# 15_BoardPowerSupply.net
KiCad netlist of a schematic drawn in Altium Designer
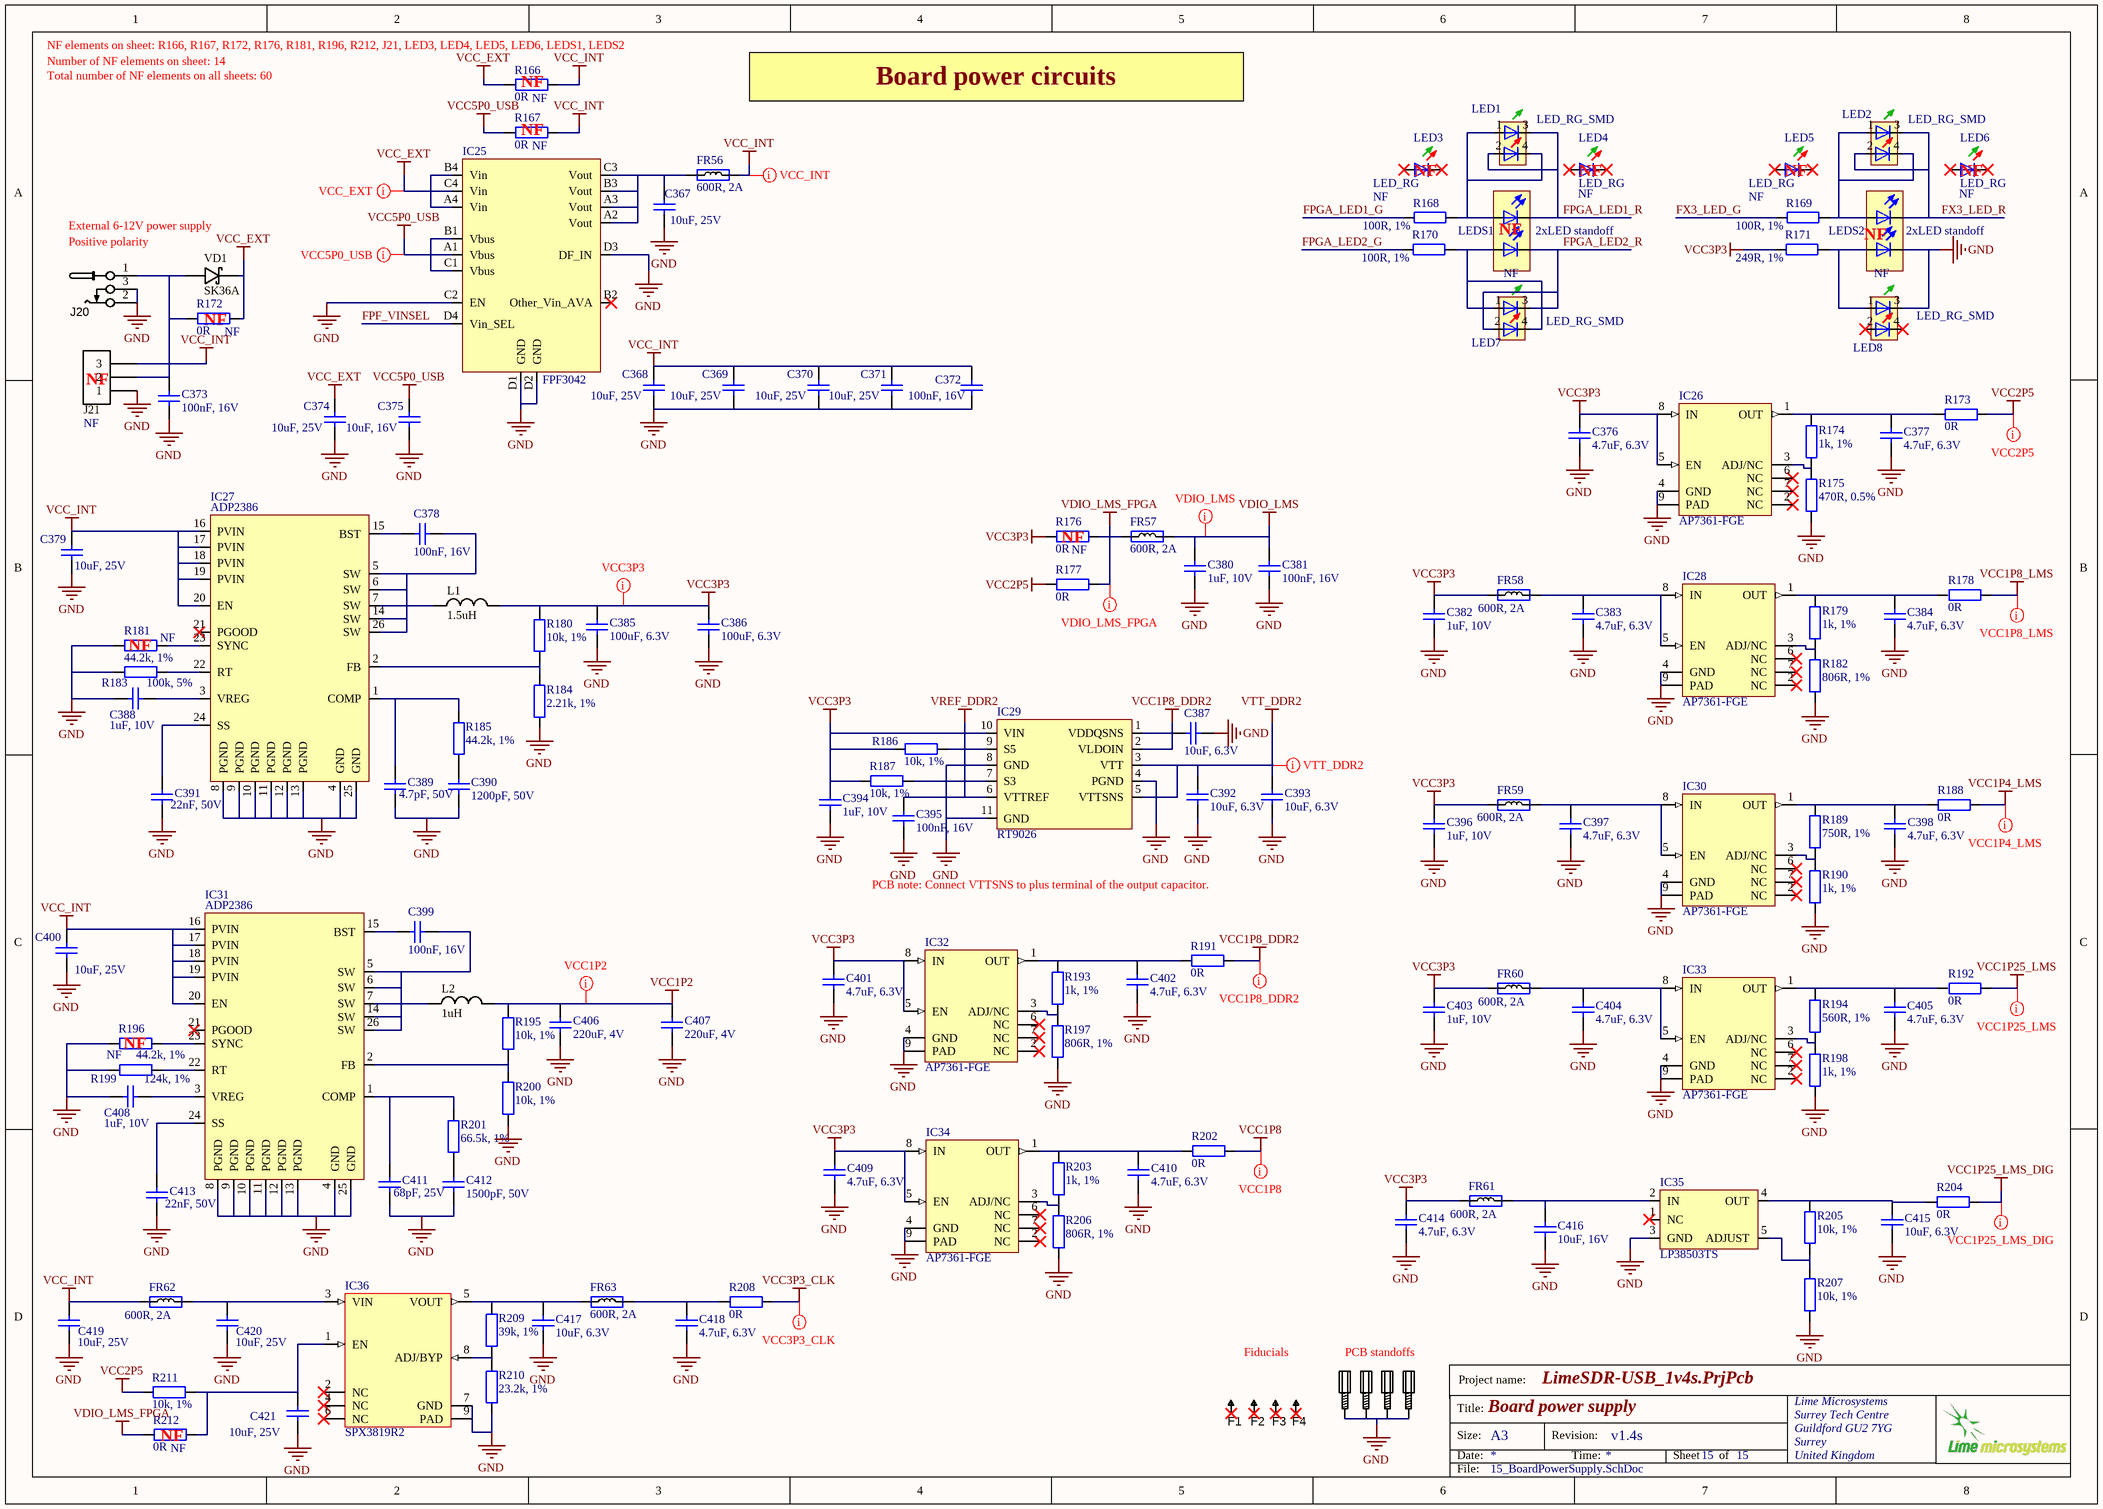
[diagram p0: 15_BoardPowerSupply.SchDoc]

(export (version "E")
  (design (tool "Eeschema 10.0.6"))
  (components
    (comp (ref "C367")
      (value "10uF, 25V")
      (footprint "CAP0603")
      (fields
        (field (name "MANUFACTURER") "Murata Electronics North America")
        (field (name "MANUFACTURER PART NUMBER") "GRM188R61E106MA73D")
        (field (name "TOLERANCE") "±20%")
      )
      (libsource (lib "LimeMicroAltiumLib_schLib") (part "Cap_0603"))
    )
    (comp (ref "C368")
      (value "10uF, 25V")
      (footprint "CAP0603")
      (fields
        (field (name "MANUFACTURER") "Murata Electronics North America")
        (field (name "MANUFACTURER PART NUMBER") "GRM188R61E106MA73D")
        (field (name "TOLERANCE") "±20%")
      )
      (libsource (lib "LimeMicroAltiumLib_schLib") (part "Cap_0603"))
    )
    (comp (ref "C369")
      (value "10uF, 25V")
      (footprint "CAP0603")
      (fields
        (field (name "MANUFACTURER") "Murata Electronics North America")
        (field (name "MANUFACTURER PART NUMBER") "GRM188R61E106MA73D")
        (field (name "TOLERANCE") "±20%")
      )
      (libsource (lib "LimeMicroAltiumLib_schLib") (part "Cap_0603"))
    )
    (comp (ref "C370")
      (value "10uF, 25V")
      (footprint "CAP0603")
      (fields
        (field (name "MANUFACTURER") "Murata Electronics North America")
        (field (name "MANUFACTURER PART NUMBER") "GRM188R61E106MA73D")
        (field (name "TOLERANCE") "±20%")
      )
      (libsource (lib "LimeMicroAltiumLib_schLib") (part "Cap_0603"))
    )
    (comp (ref "C371")
      (value "10uF, 25V")
      (footprint "CAP0603")
      (fields
        (field (name "MANUFACTURER") "Murata Electronics North America")
        (field (name "MANUFACTURER PART NUMBER") "GRM188R61E106MA73D")
        (field (name "TOLERANCE") "±20%")
      )
      (libsource (lib "LimeMicroAltiumLib_schLib") (part "Cap_0603"))
    )
    (comp (ref "C372")
      (value "100nF, 16V")
      (footprint "CAP0402")
      (fields
        (field (name "MANUFACTURER") "Murata Electronics")
        (field (name "TOLERANCE") "10 %")
        (field (name "MANUFACTURER PART NUMBER") "GRM155R71C104KA88D")
      )
      (libsource (lib "LimeMicroAltiumLib_schLib") (part "Cap_0402"))
    )
    (comp (ref "C373")
      (value "100nF, 16V")
      (footprint "CAP0402")
      (fields
        (field (name "MANUFACTURER") "Murata Electronics")
        (field (name "TOLERANCE") "10 %")
        (field (name "MANUFACTURER PART NUMBER") "GRM155R71C104KA88D")
      )
      (libsource (lib "LimeMicroAltiumLib_schLib") (part "Cap_0402"))
    )
    (comp (ref "C374")
      (value "10uF, 25V")
      (footprint "CAP0603")
      (fields
        (field (name "MANUFACTURER") "Murata Electronics North America")
        (field (name "MANUFACTURER PART NUMBER") "GRM188R61E106MA73D")
        (field (name "TOLERANCE") "±20%")
      )
      (libsource (lib "LimeMicroAltiumLib_schLib") (part "Cap_0603"))
    )
    (comp (ref "C375")
      (value "10uF, 16V")
      (footprint "CAP0603")
      (fields (field (name "MANUFACTURER") "Yageo") (field (name "TOLERANCE") "±20%"))
      (libsource (lib "LimeMicroAltiumLib_schLib") (part "Cap_0603"))
    )
    (comp (ref "C376")
      (value "4.7uF, 6.3V")
      (footprint "CAP0402")
      (fields
        (field (name "MANUFACTURER") "Murata Electronics North America")
        (field (name "TOLERANCE") "±20%")
        (field (name "MANUFACTURER PART NUMBER") "GRM155R60J475ME87D")
      )
      (libsource (lib "LimeMicroAltiumLib_schLib") (part "Cap_0402"))
    )
    (comp (ref "C377")
      (value "4.7uF, 6.3V")
      (footprint "CAP0402")
      (fields
        (field (name "MANUFACTURER") "Murata Electronics North America")
        (field (name "TOLERANCE") "±20%")
        (field (name "MANUFACTURER PART NUMBER") "GRM155R60J475ME87D")
      )
      (libsource (lib "LimeMicroAltiumLib_schLib") (part "Cap_0402"))
    )
    (comp (ref "C378")
      (value "100nF, 16V")
      (footprint "CAP0402")
      (fields
        (field (name "MANUFACTURER") "Murata Electronics")
        (field (name "TOLERANCE") "10 %")
        (field (name "MANUFACTURER PART NUMBER") "GRM155R71C104KA88D")
      )
      (libsource (lib "LimeMicroAltiumLib_schLib") (part "Cap_0402"))
    )
    (comp (ref "C379")
      (value "10uF, 25V")
      (footprint "CAP0603")
      (fields
        (field (name "MANUFACTURER") "Murata Electronics North America")
        (field (name "MANUFACTURER PART NUMBER") "GRM188R61E106MA73D")
        (field (name "TOLERANCE") "±20%")
      )
      (libsource (lib "LimeMicroAltiumLib_schLib") (part "Cap_0603"))
    )
    (comp (ref "C380")
      (value "1uF, 10V")
      (footprint "CAP0402")
      (fields (field (name "MANUFACTURER") "TDK"))
      (libsource (lib "LimeMicroAltiumLib_schLib") (part "Cap_0402"))
    )
    (comp (ref "C381")
      (value "100nF, 16V")
      (footprint "CAP0402")
      (fields
        (field (name "MANUFACTURER") "Murata Electronics")
        (field (name "TOLERANCE") "10 %")
        (field (name "MANUFACTURER PART NUMBER") "GRM155R71C104KA88D")
      )
      (libsource (lib "LimeMicroAltiumLib_schLib") (part "Cap_0402"))
    )
    (comp (ref "C382")
      (value "1uF, 10V")
      (footprint "CAP0402")
      (fields (field (name "MANUFACTURER") "TDK"))
      (libsource (lib "LimeMicroAltiumLib_schLib") (part "Cap_0402"))
    )
    (comp (ref "C383")
      (value "4.7uF, 6.3V")
      (footprint "CAP0402")
      (fields
        (field (name "MANUFACTURER") "Murata Electronics North America")
        (field (name "TOLERANCE") "±20%")
        (field (name "MANUFACTURER PART NUMBER") "GRM155R60J475ME87D")
      )
      (libsource (lib "LimeMicroAltiumLib_schLib") (part "Cap_0402"))
    )
    (comp (ref "C384")
      (value "4.7uF, 6.3V")
      (footprint "CAP0402")
      (fields
        (field (name "MANUFACTURER") "Murata Electronics North America")
        (field (name "TOLERANCE") "±20%")
        (field (name "MANUFACTURER PART NUMBER") "GRM155R60J475ME87D")
      )
      (libsource (lib "LimeMicroAltiumLib_schLib") (part "Cap_0402"))
    )
    (comp (ref "C385")
      (value "100uF, 6.3V")
      (footprint "CAP1206")
      (fields (field (name "MANUFACTURER") "Murata Electronics North America"))
      (libsource (lib "LimeFPGAboard_schLib") (part "Cap_1206"))
    )
    (comp (ref "C386")
      (value "100uF, 6.3V")
      (footprint "CAP1206")
      (fields (field (name "MANUFACTURER") "Murata Electronics North America"))
      (libsource (lib "LimeFPGAboard_schLib") (part "Cap_1206"))
    )
    (comp (ref "C387")
      (value "10uF, 6.3V")
      (footprint "CAP0603")
      (fields (field (name "TOLERANCE") "±20%") (field (name "MANUFACTURER") "Yageo"))
      (libsource (lib "LimeFPGAboard_schLib") (part "Cap_0603"))
    )
    (comp (ref "C388")
      (value "1uF, 10V")
      (footprint "CAP0402")
      (fields (field (name "MANUFACTURER") "TDK"))
      (libsource (lib "LimeMicroAltiumLib_schLib") (part "Cap_0402"))
    )
    (comp (ref "C389")
      (value "4.7pF, 50V")
      (footprint "CAP0402")
      (fields (field (name "MANUFACTURER") "Murata Electronics North America"))
      (libsource (lib "LimeMicroAltiumLib_schLib") (part "Cap_0402"))
    )
    (comp (ref "C390")
      (value "1200pF, 50V")
      (footprint "CAP0402")
      (fields (field (name "MANUFACTURER") "Kemet") (field (name "TOLERANCE") "±5%"))
      (libsource (lib "LimeMicroAltiumLib_schLib") (part "Cap_0402"))
    )
    (comp (ref "C391")
      (value "22nF, 50V")
      (footprint "CAP0402")
      (fields (field (name "TOLERANCE") "±10%") (field (name "MANUFACTURER") "Kemet"))
      (libsource (lib "LimeMicroAltiumLib_schLib") (part "Cap_0402"))
    )
    (comp (ref "C392")
      (value "10uF, 6.3V")
      (footprint "CAP0603")
      (fields (field (name "TOLERANCE") "±20%") (field (name "MANUFACTURER") "Yageo"))
      (libsource (lib "LimeFPGAboard_schLib") (part "Cap_0603"))
    )
    (comp (ref "C393")
      (value "10uF, 6.3V")
      (footprint "CAP0603")
      (fields (field (name "TOLERANCE") "±20%") (field (name "MANUFACTURER") "Yageo"))
      (libsource (lib "LimeFPGAboard_schLib") (part "Cap_0603"))
    )
    (comp (ref "C394")
      (value "1uF, 10V")
      (footprint "CAP0402")
      (fields (field (name "MANUFACTURER") "TDK"))
      (libsource (lib "LimeMicroAltiumLib_schLib") (part "Cap_0402"))
    )
    (comp (ref "C395")
      (value "100nF, 16V")
      (footprint "CAP0402")
      (fields
        (field (name "MANUFACTURER") "Murata Electronics")
        (field (name "TOLERANCE") "10 %")
        (field (name "MANUFACTURER PART NUMBER") "GRM155R71C104KA88D")
      )
      (libsource (lib "LimeMicroAltiumLib_schLib") (part "Cap_0402"))
    )
    (comp (ref "C396")
      (value "1uF, 10V")
      (footprint "CAP0402")
      (fields (field (name "MANUFACTURER") "TDK"))
      (libsource (lib "LimeMicroAltiumLib_schLib") (part "Cap_0402"))
    )
    (comp (ref "C397")
      (value "4.7uF, 6.3V")
      (footprint "CAP0402")
      (fields
        (field (name "MANUFACTURER") "Murata Electronics North America")
        (field (name "TOLERANCE") "±20%")
        (field (name "MANUFACTURER PART NUMBER") "GRM155R60J475ME87D")
      )
      (libsource (lib "LimeMicroAltiumLib_schLib") (part "Cap_0402"))
    )
    (comp (ref "C398")
      (value "4.7uF, 6.3V")
      (footprint "CAP0402")
      (fields
        (field (name "MANUFACTURER") "Murata Electronics North America")
        (field (name "TOLERANCE") "±20%")
        (field (name "MANUFACTURER PART NUMBER") "GRM155R60J475ME87D")
      )
      (libsource (lib "LimeMicroAltiumLib_schLib") (part "Cap_0402"))
    )
    (comp (ref "C399")
      (value "100nF, 16V")
      (footprint "CAP0402")
      (fields
        (field (name "MANUFACTURER") "Murata Electronics")
        (field (name "TOLERANCE") "10 %")
        (field (name "MANUFACTURER PART NUMBER") "GRM155R71C104KA88D")
      )
      (libsource (lib "LimeMicroAltiumLib_schLib") (part "Cap_0402"))
    )
    (comp (ref "C400")
      (value "10uF, 25V")
      (footprint "CAP0603")
      (fields
        (field (name "MANUFACTURER") "Murata Electronics North America")
        (field (name "MANUFACTURER PART NUMBER") "GRM188R61E106MA73D")
        (field (name "TOLERANCE") "±20%")
      )
      (libsource (lib "LimeMicroAltiumLib_schLib") (part "Cap_0603"))
    )
    (comp (ref "C401")
      (value "4.7uF, 6.3V")
      (footprint "CAP0402")
      (fields
        (field (name "MANUFACTURER") "Murata Electronics North America")
        (field (name "TOLERANCE") "±20%")
        (field (name "MANUFACTURER PART NUMBER") "GRM155R60J475ME87D")
      )
      (libsource (lib "LimeMicroAltiumLib_schLib") (part "Cap_0402"))
    )
    (comp (ref "C402")
      (value "4.7uF, 6.3V")
      (footprint "CAP0402")
      (fields
        (field (name "MANUFACTURER") "Murata Electronics North America")
        (field (name "TOLERANCE") "±20%")
        (field (name "MANUFACTURER PART NUMBER") "GRM155R60J475ME87D")
      )
      (libsource (lib "LimeMicroAltiumLib_schLib") (part "Cap_0402"))
    )
    (comp (ref "C403")
      (value "1uF, 10V")
      (footprint "CAP0402")
      (fields (field (name "MANUFACTURER") "TDK"))
      (libsource (lib "LimeMicroAltiumLib_schLib") (part "Cap_0402"))
    )
    (comp (ref "C404")
      (value "4.7uF, 6.3V")
      (footprint "CAP0402")
      (fields
        (field (name "MANUFACTURER") "Murata Electronics North America")
        (field (name "TOLERANCE") "±20%")
        (field (name "MANUFACTURER PART NUMBER") "GRM155R60J475ME87D")
      )
      (libsource (lib "LimeMicroAltiumLib_schLib") (part "Cap_0402"))
    )
    (comp (ref "C405")
      (value "4.7uF, 6.3V")
      (footprint "CAP0402")
      (fields
        (field (name "MANUFACTURER") "Murata Electronics North America")
        (field (name "TOLERANCE") "±20%")
        (field (name "MANUFACTURER PART NUMBER") "GRM155R60J475ME87D")
      )
      (libsource (lib "LimeMicroAltiumLib_schLib") (part "Cap_0402"))
    )
    (comp (ref "C406")
      (value "220uF, 4V")
      (footprint "CAP1206")
      (fields
        (field (name "MANUFACTURER") "Murata Electronics North America")
        (field (name "TOLERANCE") "±20%")
        (field (name "MANUFACTURER PART NUMBER") "GRM31CR60G227ME11L")
      )
      (libsource (lib "LimeFPGAboard_schLib") (part "Cap_1206"))
    )
    (comp (ref "C407")
      (value "220uF, 4V")
      (footprint "CAP1206")
      (fields
        (field (name "MANUFACTURER") "Murata Electronics North America")
        (field (name "TOLERANCE") "±20%")
        (field (name "MANUFACTURER PART NUMBER") "GRM31CR60G227ME11L")
      )
      (libsource (lib "LimeFPGAboard_schLib") (part "Cap_1206"))
    )
    (comp (ref "C408")
      (value "1uF, 10V")
      (footprint "CAP0402")
      (fields (field (name "MANUFACTURER") "TDK"))
      (libsource (lib "LimeMicroAltiumLib_schLib") (part "Cap_0402"))
    )
    (comp (ref "C409")
      (value "4.7uF, 6.3V")
      (footprint "CAP0402")
      (fields
        (field (name "MANUFACTURER") "Murata Electronics North America")
        (field (name "TOLERANCE") "±20%")
        (field (name "MANUFACTURER PART NUMBER") "GRM155R60J475ME87D")
      )
      (libsource (lib "LimeMicroAltiumLib_schLib") (part "Cap_0402"))
    )
    (comp (ref "C410")
      (value "4.7uF, 6.3V")
      (footprint "CAP0402")
      (fields
        (field (name "MANUFACTURER") "Murata Electronics North America")
        (field (name "TOLERANCE") "±20%")
        (field (name "MANUFACTURER PART NUMBER") "GRM155R60J475ME87D")
      )
      (libsource (lib "LimeMicroAltiumLib_schLib") (part "Cap_0402"))
    )
    (comp (ref "C411")
      (value "68pF, 25V")
      (footprint "CAP0402")
      (fields (field (name "TOLERANCE") "±1%") (field (name "MANUFACTURER") "Kemet"))
      (libsource (lib "LimeMicroAltiumLib_schLib") (part "Cap_0402"))
    )
    (comp (ref "C412")
      (value "1500pF, 50V")
      (footprint "CAP0402")
      (fields
        (field (name "MANUFACTURER") "Samsung Electro-Mechanics America, Inc.")
        (field (name "TOLERANCE") "±10%")
      )
      (libsource (lib "LimeMicroAltiumLib_schLib") (part "Cap_0402"))
    )
    (comp (ref "C413")
      (value "22nF, 50V")
      (footprint "CAP0402")
      (fields (field (name "TOLERANCE") "±10%") (field (name "MANUFACTURER") "Kemet"))
      (libsource (lib "LimeMicroAltiumLib_schLib") (part "Cap_0402"))
    )
    (comp (ref "C414")
      (value "4.7uF, 6.3V")
      (footprint "CAP0402")
      (fields
        (field (name "MANUFACTURER") "Murata Electronics North America")
        (field (name "TOLERANCE") "±20%")
        (field (name "MANUFACTURER PART NUMBER") "GRM155R60J475ME87D")
      )
      (libsource (lib "LimeMicroAltiumLib_schLib") (part "Cap_0402"))
    )
    (comp (ref "C415")
      (value "10uF, 6.3V")
      (footprint "CAP0603")
      (fields (field (name "TOLERANCE") "±20%") (field (name "MANUFACTURER") "Yageo"))
      (libsource (lib "LimeFPGAboard_schLib") (part "Cap_0603"))
    )
    (comp (ref "C416")
      (value "10uF, 16V")
      (footprint "CAP0603")
      (fields (field (name "MANUFACTURER") "Yageo") (field (name "TOLERANCE") "±20%"))
      (libsource (lib "LimeMicroAltiumLib_schLib") (part "Cap_0603"))
    )
    (comp (ref "C417")
      (value "10uF, 6.3V")
      (footprint "CAP0603")
      (fields (field (name "TOLERANCE") "±20%") (field (name "MANUFACTURER") "Yageo"))
      (libsource (lib "LimeFPGAboard_schLib") (part "Cap_0603"))
    )
    (comp (ref "C418")
      (value "4.7uF, 6.3V")
      (footprint "CAP0402")
      (fields
        (field (name "MANUFACTURER") "Murata Electronics North America")
        (field (name "TOLERANCE") "±20%")
        (field (name "MANUFACTURER PART NUMBER") "GRM155R60J475ME87D")
      )
      (libsource (lib "LimeMicroAltiumLib_schLib") (part "Cap_0402"))
    )
    (comp (ref "C419")
      (value "10uF, 25V")
      (footprint "CAP0603")
      (fields
        (field (name "MANUFACTURER") "Murata Electronics North America")
        (field (name "MANUFACTURER PART NUMBER") "GRM188R61E106MA73D")
        (field (name "TOLERANCE") "±20%")
      )
      (libsource (lib "LimeMicroAltiumLib_schLib") (part "Cap_0603"))
    )
    (comp (ref "C420")
      (value "10uF, 25V")
      (footprint "CAP0603")
      (fields
        (field (name "MANUFACTURER") "Murata Electronics North America")
        (field (name "MANUFACTURER PART NUMBER") "GRM188R61E106MA73D")
        (field (name "TOLERANCE") "±20%")
      )
      (libsource (lib "LimeMicroAltiumLib_schLib") (part "Cap_0603"))
    )
    (comp (ref "C421")
      (value "10uF, 25V")
      (footprint "CAP0603")
      (fields
        (field (name "MANUFACTURER") "Murata Electronics North America")
        (field (name "MANUFACTURER PART NUMBER") "GRM188R61E106MA73D")
        (field (name "TOLERANCE") "±20%")
      )
      (libsource (lib "LimeMicroAltiumLib_schLib") (part "Cap_0603"))
    )
    (comp (ref "F1")
      (value "Fiducial")
      (footprint "Fiducial")
      (libsource (lib "VGTU_Altium_lib") (part "Fiducial"))
    )
    (comp (ref "F2")
      (value "Fiducial")
      (footprint "Fiducial")
      (libsource (lib "VGTU_Altium_lib") (part "Fiducial"))
    )
    (comp (ref "F3")
      (value "Fiducial")
      (footprint "Fiducial")
      (libsource (lib "VGTU_Altium_lib") (part "Fiducial"))
    )
    (comp (ref "F4")
      (value "Fiducial")
      (footprint "Fiducial")
      (libsource (lib "VGTU_Altium_lib") (part "Fiducial"))
    )
    (comp (ref "FR56")
      (value "600R, 2A")
      (footprint "RES0805")
      (fields (field (name "MANUFACTURER") "TDK Corporation"))
      (libsource (lib "LimeFPGAboard_schLib") (part "Ferrite"))
    )
    (comp (ref "FR57")
      (value "600R, 2A")
      (footprint "RES0805")
      (fields (field (name "MANUFACTURER") "TDK Corporation"))
      (libsource (lib "LimeMicroAltiumLib_schLib") (part "Ferrite"))
    )
    (comp (ref "FR58")
      (value "600R, 2A")
      (footprint "RES0805")
      (fields (field (name "MANUFACTURER") "TDK Corporation"))
      (libsource (lib "LimeMicroAltiumLib_schLib") (part "Ferrite"))
    )
    (comp (ref "FR59")
      (value "600R, 2A")
      (footprint "RES0805")
      (fields (field (name "MANUFACTURER") "TDK Corporation"))
      (libsource (lib "LimeMicroAltiumLib_schLib") (part "Ferrite"))
    )
    (comp (ref "FR60")
      (value "600R, 2A")
      (footprint "RES0805")
      (fields (field (name "MANUFACTURER") "TDK Corporation"))
      (libsource (lib "LimeMicroAltiumLib_schLib") (part "Ferrite"))
    )
    (comp (ref "FR61")
      (value "600R, 2A")
      (footprint "RES0805")
      (fields (field (name "MANUFACTURER") "TDK Corporation"))
      (libsource (lib "LimeMicroAltiumLib_schLib") (part "Ferrite"))
    )
    (comp (ref "FR62")
      (value "600R, 2A")
      (footprint "RES0805")
      (fields (field (name "MANUFACTURER") "TDK Corporation"))
      (libsource (lib "LimeMicroAltiumLib_schLib") (part "Ferrite"))
    )
    (comp (ref "FR63")
      (value "600R, 2A")
      (footprint "RES0805")
      (fields (field (name "MANUFACTURER") "TDK Corporation"))
      (libsource (lib "LimeMicroAltiumLib_schLib") (part "Ferrite"))
    )
    (comp (ref "IC25")
      (value "FPF3042")
      (footprint "FPF3042")
      (fields (field (name "MANUFACTURER") "Fairchild Semiconductor"))
      (libsource (lib "LimeMicroAltiumLib_schLib") (part "FPF3042"))
    )
    (comp (ref "IC26")
      (value "AP7361-FGE")
      (footprint "AP7361")
      (fields
        (field (name "MANUFACTURER PART NUMBER") "AP7361-FGE-7")
        (field (name "MANUFACTURER") "Diodes Incorporated")
      )
      (libsource (lib "LimeMicroAltiumLib_schLib") (part "AP7361"))
    )
    (comp (ref "IC27")
      (value "ADP2386")
      (footprint "ADP2386")
      (fields
        (field (name "MANUFACTURER PART NUMBER") "ADP2386ACPZN-R7")
        (field (name "MANUFACTURER") "Analog Devices Inc.")
      )
      (libsource (lib "LimeMicroAltiumLib_schLib") (part "ADP2386"))
    )
    (comp (ref "IC28")
      (value "AP7361-FGE")
      (footprint "AP7361")
      (fields
        (field (name "MANUFACTURER PART NUMBER") "AP7361-FGE-7")
        (field (name "MANUFACTURER") "Diodes Incorporated")
      )
      (libsource (lib "LimeMicroAltiumLib_schLib") (part "AP7361"))
    )
    (comp (ref "IC29")
      (value "RT9026")
      (footprint "MSOP10")
      (fields (field (name "MANUFACTURER") "Richtek USA Inc."))
      (libsource (lib "LimeMicroAltiumLib_schLib") (part "RT9026"))
    )
    (comp (ref "IC30")
      (value "AP7361-FGE")
      (footprint "AP7361")
      (fields
        (field (name "MANUFACTURER PART NUMBER") "AP7361-FGE-7")
        (field (name "MANUFACTURER") "Diodes Incorporated")
      )
      (libsource (lib "LimeMicroAltiumLib_schLib") (part "AP7361"))
    )
    (comp (ref "IC31")
      (value "ADP2386")
      (footprint "ADP2386")
      (fields (field (name "MANUFACTURER") "Analog Devices Inc."))
      (libsource (lib "LimeMicroAltiumLib_schLib") (part "ADP2386"))
    )
    (comp (ref "IC32")
      (value "AP7361-FGE")
      (footprint "AP7361")
      (fields
        (field (name "MANUFACTURER PART NUMBER") "AP7361-FGE-7")
        (field (name "MANUFACTURER") "Diodes Incorporated")
      )
      (libsource (lib "LimeMicroAltiumLib_schLib") (part "AP7361"))
    )
    (comp (ref "IC33")
      (value "AP7361-FGE")
      (footprint "AP7361")
      (fields
        (field (name "MANUFACTURER PART NUMBER") "AP7361-FGE-7")
        (field (name "MANUFACTURER") "Diodes Incorporated")
      )
      (libsource (lib "LimeMicroAltiumLib_schLib") (part "AP7361"))
    )
    (comp (ref "IC34")
      (value "AP7361-FGE")
      (footprint "AP7361")
      (fields
        (field (name "MANUFACTURER PART NUMBER") "AP7361-FGE-7")
        (field (name "MANUFACTURER") "Diodes Incorporated")
      )
      (libsource (lib "LimeMicroAltiumLib_schLib") (part "AP7361"))
    )
    (comp (ref "IC35")
      (value "LP38503TS")
      (footprint "TO-263-5_v2")
      (fields
        (field (name "MANUFACTURER PART NUMBER") "LP38503TS-ADJ/NOPB")
        (field (name "MANUFACTURER") "Texas Instruments")
      )
      (libsource (lib "LimeMicroAltiumLib_schLib") (part "LP38503TS"))
    )
    (comp (ref "IC36")
      (value "SPX3819R2")
      (footprint "SPX3819R2-L/TR")
      (fields (field (name "MANUFACTURER") "Exar Corporation"))
      (libsource (lib "LimeMicroAltiumLib_schLib") (part "SPX3819R2-L/TR"))
    )
    (comp (ref "J20")
      (value "CONN_PWR_JACK_2.1x5.5mm")
      (footprint "CONN_PWR_JACK_v4")
      (description "Power Connector, THT, 2.1mm ID, 5.5mm OD")
      (fields (field (name "MANUFACTURER") "CUI Inc."))
      (libsource (lib "LimeFPGAboard_schLib") (part "CONN_PWR_JACK_2.1x5.5mm"))
    )
    (comp (ref "J21")
      (value "Header 3x1 pin")
      (footprint "HDR_1x3")
      (description "Header, 3-pin")
      (fields (field (name "ASSEMBLY INFO") "NF") (field (name "MANUFACTURER") "Amphenol FCI"))
      (libsource (lib "LimeMicroAltiumLib_schLib") (part "Header3P"))
    )
    (comp (ref "L1")
      (value "1.5uH")
      (footprint "FDVE1040_TOKO_INDUCTOR")
      (fields (field (name "MANUFACTURER") "Vishay Dale") (field (name "TOLERANCE") "±20%"))
      (libsource (lib "LimeMicroAltiumLib_schLib") (part "Inductor_0603"))
    )
    (comp (ref "L2")
      (value "1uH")
      (footprint "FDVE1040_TOKO_INDUCTOR")
      (fields (field (name "TOLERANCE") "±20%") (field (name "MANUFACTURER") "Vishay Dale"))
      (libsource (lib "LimeMicroAltiumLib_schLib") (part "Inductor_0603"))
    )
    (comp (ref "LED1")
      (value "LED_RG_SMD")
      (footprint "LED-2x0603")
      (fields (field (name "MANUFACTURER") "Avago Technologies US Inc."))
      (libsource (lib "LimeMicroAltiumLib_schLib") (part "LED_green_red_SMD"))
    )
    (comp (ref "LED2")
      (value "LED_RG_SMD")
      (footprint "LED-2x0603")
      (fields (field (name "MANUFACTURER") "Avago Technologies US Inc."))
      (libsource (lib "LimeMicroAltiumLib_schLib") (part "LED_green_red_SMD"))
    )
    (comp (ref "LED3")
      (value "LED_RG")
      (fields
        (field (name "MANUFACTURER") "Visual Communications Company - VCC")
        (field (name "ASSEMBLY INFO") "NF")
      )
      (libsource (lib "LimeMicroAltiumLib_schLib") (part "LED_green_red"))
    )
    (comp (ref "LED4")
      (value "LED_RG")
      (fields
        (field (name "MANUFACTURER") "Visual Communications Company - VCC")
        (field (name "ASSEMBLY INFO") "NF")
      )
      (libsource (lib "LimeMicroAltiumLib_schLib") (part "LED_green_red"))
    )
    (comp (ref "LED5")
      (value "LED_RG")
      (fields
        (field (name "MANUFACTURER") "Visual Communications Company - VCC")
        (field (name "ASSEMBLY INFO") "NF")
      )
      (libsource (lib "LimeMicroAltiumLib_schLib") (part "LED_green_red"))
    )
    (comp (ref "LED6")
      (value "LED_RG")
      (fields
        (field (name "MANUFACTURER") "Visual Communications Company - VCC")
        (field (name "ASSEMBLY INFO") "NF")
      )
      (libsource (lib "LimeMicroAltiumLib_schLib") (part "LED_green_red"))
    )
    (comp (ref "LED7")
      (value "LED_RG_SMD")
      (footprint "LED-2x0603")
      (fields (field (name "MANUFACTURER") "Avago Technologies US Inc."))
      (libsource (lib "LimeMicroAltiumLib_schLib") (part "LED_green_red_SMD"))
    )
    (comp (ref "LED8")
      (value "LED_RG_SMD")
      (footprint "LED-2x0603")
      (fields (field (name "MANUFACTURER") "Avago Technologies US Inc."))
      (libsource (lib "LimeMicroAltiumLib_schLib") (part "LED_green_red_SMD"))
    )
    (comp (ref "LEDS1")
      (value "2xLED standoff")
      (footprint "LED_STANDOFF_H-201C")
      (fields (field (name "MANUFACTURER") "Bivar Inc.") (field (name "ASSEMBLY INFO") "NF"))
      (libsource (lib "LimeMicroAltiumLib_schLib") (part "LEDx2_STANDOFF"))
    )
    (comp (ref "LEDS2")
      (value "2xLED standoff")
      (footprint "LED_STANDOFF_H-201C")
      (fields (field (name "MANUFACTURER") "Bivar Inc.") (field (name "ASSEMBLY INFO") "NF"))
      (libsource (lib "LimeMicroAltiumLib_schLib") (part "LEDx2_STANDOFF"))
    )
    (comp (ref "MECH1")
      (value "# pcs.")
      (footprint "PCB_standoff")
      (description "STANDOFF M/F MET 5MM HEX 10MM L")
      (fields (field (name "MANUFACTURER") "FIX&FASTEN"))
      (libsource (lib "LimeMicroAltiumLib_schLib") (part "STANDOFF_M-F_THREADED_M3x8x10mm_HEX_5mm dia"))
    )
    (comp (ref "MECH2")
      (value "# pcs.")
      (footprint "PCB_standoff")
      (description "STANDOFF M/F MET 5MM HEX 10MM L")
      (fields (field (name "MANUFACTURER") "FIX&FASTEN"))
      (libsource (lib "LimeMicroAltiumLib_schLib") (part "STANDOFF_M-F_THREADED_M3x8x10mm_HEX_5mm dia"))
    )
    (comp (ref "MECH3")
      (value "# pcs.")
      (footprint "PCB_standoff")
      (description "STANDOFF M/F MET 5MM HEX 10MM L")
      (fields (field (name "MANUFACTURER") "FIX&FASTEN"))
      (libsource (lib "LimeMicroAltiumLib_schLib") (part "STANDOFF_M-F_THREADED_M3x8x10mm_HEX_5mm dia"))
    )
    (comp (ref "MECH4")
      (value "# pcs.")
      (footprint "PCB_standoff")
      (description "STANDOFF M/F MET 5MM HEX 10MM L")
      (fields (field (name "MANUFACTURER") "FIX&FASTEN"))
      (libsource (lib "LimeMicroAltiumLib_schLib") (part "STANDOFF_M-F_THREADED_M3x8x10mm_HEX_5mm dia"))
    )
    (comp (ref "R166")
      (value "0R")
      (footprint "RES0402")
      (fields
        (field (name "ASSEMBLY INFO") "NF")
        (field (name "MANUFACTURER") "Yageo")
        (field (name "TOLERANCE") "Jumper")
      )
      (libsource (lib "LimeMicroAltiumLib_schLib") (part "Res_0402"))
    )
    (comp (ref "R167")
      (value "0R")
      (footprint "RES0402")
      (fields
        (field (name "ASSEMBLY INFO") "NF")
        (field (name "MANUFACTURER") "Yageo")
        (field (name "TOLERANCE") "Jumper")
      )
      (libsource (lib "LimeMicroAltiumLib_schLib") (part "Res_0402"))
    )
    (comp (ref "R168")
      (value "100R, 1%")
      (footprint "RES0402")
      (fields (field (name "TOLERANCE") "±1%") (field (name "MANUFACTURER") "Stackpole Electronics Inc."))
      (libsource (lib "LimeMicroAltiumLib_schLib") (part "Res_0402"))
    )
    (comp (ref "R169")
      (value "100R, 1%")
      (footprint "RES0402")
      (fields (field (name "TOLERANCE") "±1%") (field (name "MANUFACTURER") "Stackpole Electronics Inc."))
      (libsource (lib "LimeMicroAltiumLib_schLib") (part "Res_0402"))
    )
    (comp (ref "R170")
      (value "100R, 1%")
      (footprint "RES0402")
      (fields (field (name "TOLERANCE") "±1%") (field (name "MANUFACTURER") "Stackpole Electronics Inc."))
      (libsource (lib "LimeMicroAltiumLib_schLib") (part "Res_0402"))
    )
    (comp (ref "R171")
      (value "249R, 1%")
      (footprint "RES0402")
      (fields (field (name "MANUFACTURER") "Stackpole Electronics Inc") (field (name "TOLERANCE") "±1%"))
      (libsource (lib "LimeMicroAltiumLib_schLib") (part "Res_0402"))
    )
    (comp (ref "R172")
      (value "0R")
      (footprint "RES0805")
      (fields
        (field (name "ASSEMBLY INFO") "NF")
        (field (name "MANUFACTURER") "Vishay Dale")
        (field (name "TOLERANCE") "Jumper")
      )
      (libsource (lib "LimeMicroAltiumLib_schLib") (part "Res_0402"))
    )
    (comp (ref "R173")
      (value "0R")
      (footprint "RES0402")
      (fields (field (name "MANUFACTURER") "Yageo") (field (name "TOLERANCE") "Jumper"))
      (libsource (lib "LimeMicroAltiumLib_schLib") (part "Res_0402"))
    )
    (comp (ref "R174")
      (value "1k, 1%")
      (footprint "RES0402")
      (fields (field (name "MANUFACTURER") "Stackpole Electronics Inc") (field (name "TOLERANCE") "±1%"))
      (libsource (lib "LimeMicroAltiumLib_schLib") (part "Res_0402"))
    )
    (comp (ref "R175")
      (value "470R, 0.5%")
      (footprint "RES0402")
      (fields
        (field (name "TOLERANCE") "±0.5%")
        (field (name "MANUFACTURER") "Panasonic Electronic Components")
      )
      (libsource (lib "LimeMicroAltiumLib_schLib") (part "Res_0402"))
    )
    (comp (ref "R176")
      (value "0R")
      (footprint "RES0402")
      (fields
        (field (name "ASSEMBLY INFO") "NF")
        (field (name "MANUFACTURER") "Yageo")
        (field (name "TOLERANCE") "Jumper")
      )
      (libsource (lib "LimeMicroAltiumLib_schLib") (part "Res_0402"))
    )
    (comp (ref "R177")
      (value "0R")
      (footprint "RES0402")
      (fields (field (name "MANUFACTURER") "Yageo") (field (name "TOLERANCE") "Jumper"))
      (libsource (lib "LimeMicroAltiumLib_schLib") (part "Res_0402"))
    )
    (comp (ref "R178")
      (value "0R")
      (footprint "RES0402")
      (fields (field (name "MANUFACTURER") "Yageo") (field (name "TOLERANCE") "Jumper"))
      (libsource (lib "LimeMicroAltiumLib_schLib") (part "Res_0402"))
    )
    (comp (ref "R179")
      (value "1k, 1%")
      (footprint "RES0402")
      (fields (field (name "MANUFACTURER") "Stackpole Electronics Inc") (field (name "TOLERANCE") "±1%"))
      (libsource (lib "LimeMicroAltiumLib_schLib") (part "Res_0402"))
    )
    (comp (ref "R180")
      (value "10k, 1%")
      (footprint "RES0402")
      (fields (field (name "MANUFACTURER") "Yageo") (field (name "TOLERANCE") "±1%"))
      (libsource (lib "LimeMicroAltiumLib_schLib") (part "Res_0402"))
    )
    (comp (ref "R181")
      (value "44.2k, 1%")
      (footprint "RES0402")
      (fields
        (field (name "ASSEMBLY INFO") "NF")
        (field (name "TOLERANCE") "±1%")
        (field (name "MANUFACTURER") "Panasonic Electronic Components")
      )
      (libsource (lib "LimeMicroAltiumLib_schLib") (part "Res_0402"))
    )
    (comp (ref "R182")
      (value "806R, 1%")
      (footprint "RES0402")
      (fields (field (name "TOLERANCE") "±1%") (field (name "MANUFACTURER") "Stackpole Electronics Inc"))
      (libsource (lib "LimeMicroAltiumLib_schLib") (part "Res_0402"))
    )
    (comp (ref "R183")
      (value "100k, 5%")
      (footprint "RES0402")
      (fields
        (field (name "MANUFACTURER") "Panasonic Electronic Components")
        (field (name "MANUFACTURER PART NUMBER") "ERJ-2GEJ104X")
        (field (name "TOLERANCE") "±5%")
      )
      (libsource (lib "LimeMicroAltiumLib_schLib") (part "Res_0402"))
    )
    (comp (ref "R184")
      (value "2.21k, 1%")
      (footprint "RES0402")
      (fields (field (name "MANUFACTURER") "Stackpole Electronics Inc.") (field (name "TOLERANCE") "±1%"))
      (libsource (lib "LimeMicroAltiumLib_schLib") (part "Res_0402"))
    )
    (comp (ref "R185")
      (value "44.2k, 1%")
      (footprint "RES0402")
      (fields
        (field (name "TOLERANCE") "±1%")
        (field (name "MANUFACTURER") "Panasonic Electronic Components")
      )
      (libsource (lib "LimeMicroAltiumLib_schLib") (part "Res_0402"))
    )
    (comp (ref "R186")
      (value "10k, 1%")
      (footprint "RES0402")
      (fields (field (name "MANUFACTURER") "Yageo") (field (name "TOLERANCE") "±1%"))
      (libsource (lib "LimeMicroAltiumLib_schLib") (part "Res_0402"))
    )
    (comp (ref "R187")
      (value "10k, 1%")
      (footprint "RES0402")
      (fields (field (name "MANUFACTURER") "Yageo") (field (name "TOLERANCE") "±1%"))
      (libsource (lib "LimeMicroAltiumLib_schLib") (part "Res_0402"))
    )
    (comp (ref "R188")
      (value "0R")
      (footprint "RES0402")
      (fields (field (name "MANUFACTURER") "Yageo") (field (name "TOLERANCE") "Jumper"))
      (libsource (lib "LimeMicroAltiumLib_schLib") (part "Res_0402"))
    )
    (comp (ref "R189")
      (value "750R, 1%")
      (footprint "RES0402")
      (fields
        (field (name "TOLERANCE") "±1%")
        (field (name "MANUFACTURER PART NUMBER") "RC0402FR-07750RL")
        (field (name "MANUFACTURER") "Yageo")
      )
      (libsource (lib "LimeMicroAltiumLib_schLib") (part "Res_0402"))
    )
    (comp (ref "R190")
      (value "1k, 1%")
      (footprint "RES0402")
      (fields (field (name "MANUFACTURER") "Stackpole Electronics Inc") (field (name "TOLERANCE") "±1%"))
      (libsource (lib "LimeMicroAltiumLib_schLib") (part "Res_0402"))
    )
    (comp (ref "R191")
      (value "0R")
      (footprint "RES0402")
      (fields (field (name "MANUFACTURER") "Yageo") (field (name "TOLERANCE") "Jumper"))
      (libsource (lib "LimeMicroAltiumLib_schLib") (part "Res_0402"))
    )
    (comp (ref "R192")
      (value "0R")
      (footprint "RES0402")
      (fields (field (name "MANUFACTURER") "Yageo") (field (name "TOLERANCE") "Jumper"))
      (libsource (lib "LimeMicroAltiumLib_schLib") (part "Res_0402"))
    )
    (comp (ref "R193")
      (value "1k, 1%")
      (footprint "RES0402")
      (fields (field (name "MANUFACTURER") "Stackpole Electronics Inc") (field (name "TOLERANCE") "±1%"))
      (libsource (lib "LimeMicroAltiumLib_schLib") (part "Res_0402"))
    )
    (comp (ref "R194")
      (value "560R, 1%")
      (footprint "RES0402")
      (fields
        (field (name "MANUFACTURER PART NUMBER") "CRCW0402560RFKED")
        (field (name "TOLERANCE") "±1%")
        (field (name "MANUFACTURER") "Vishay Dale")
      )
      (libsource (lib "LimeMicroAltiumLib_schLib") (part "Res_0402"))
    )
    (comp (ref "R195")
      (value "10k, 1%")
      (footprint "RES0402")
      (fields (field (name "MANUFACTURER") "Yageo") (field (name "TOLERANCE") "±1%"))
      (libsource (lib "LimeMicroAltiumLib_schLib") (part "Res_0402"))
    )
    (comp (ref "R196")
      (value "44.2k, 1%")
      (footprint "RES0402")
      (fields
        (field (name "ASSEMBLY INFO") "NF")
        (field (name "TOLERANCE") "±1%")
        (field (name "MANUFACTURER") "Panasonic Electronic Components")
      )
      (libsource (lib "LimeMicroAltiumLib_schLib") (part "Res_0402"))
    )
    (comp (ref "R197")
      (value "806R, 1%")
      (footprint "RES0402")
      (fields (field (name "TOLERANCE") "±1%") (field (name "MANUFACTURER") "Stackpole Electronics Inc"))
      (libsource (lib "LimeMicroAltiumLib_schLib") (part "Res_0402"))
    )
    (comp (ref "R198")
      (value "1k, 1%")
      (footprint "RES0402")
      (fields (field (name "MANUFACTURER") "Stackpole Electronics Inc") (field (name "TOLERANCE") "±1%"))
      (libsource (lib "LimeMicroAltiumLib_schLib") (part "Res_0402"))
    )
    (comp (ref "R199")
      (value "124k, 1%")
      (footprint "RES0402")
      (fields
        (field (name "MANUFACTURER") "Panasonic Electronic Components")
        (field (name "TOLERANCE") "±1%")
      )
      (libsource (lib "LimeMicroAltiumLib_schLib") (part "Res_0402"))
    )
    (comp (ref "R200")
      (value "10k, 1%")
      (footprint "RES0402")
      (fields (field (name "MANUFACTURER") "Yageo") (field (name "TOLERANCE") "±1%"))
      (libsource (lib "LimeMicroAltiumLib_schLib") (part "Res_0402"))
    )
    (comp (ref "R201")
      (value "66.5k, 1%")
      (footprint "RES0402")
      (fields
        (field (name "MANUFACTURER") "Panasonic Electronic Components")
        (field (name "TOLERANCE") "±1%")
      )
      (libsource (lib "LimeMicroAltiumLib_schLib") (part "Res_0402"))
    )
    (comp (ref "R202")
      (value "0R")
      (footprint "RES0402")
      (fields (field (name "MANUFACTURER") "Yageo") (field (name "TOLERANCE") "Jumper"))
      (libsource (lib "LimeMicroAltiumLib_schLib") (part "Res_0402"))
    )
    (comp (ref "R203")
      (value "1k, 1%")
      (footprint "RES0402")
      (fields (field (name "MANUFACTURER") "Stackpole Electronics Inc") (field (name "TOLERANCE") "±1%"))
      (libsource (lib "LimeMicroAltiumLib_schLib") (part "Res_0402"))
    )
    (comp (ref "R204")
      (value "0R")
      (footprint "RES0402")
      (fields (field (name "MANUFACTURER") "Yageo") (field (name "TOLERANCE") "Jumper"))
      (libsource (lib "LimeMicroAltiumLib_schLib") (part "Res_0402"))
    )
    (comp (ref "R205")
      (value "10k, 1%")
      (footprint "RES0402")
      (fields (field (name "MANUFACTURER") "Yageo") (field (name "TOLERANCE") "±1%"))
      (libsource (lib "LimeMicroAltiumLib_schLib") (part "Res_0402"))
    )
    (comp (ref "R206")
      (value "806R, 1%")
      (footprint "RES0402")
      (fields (field (name "TOLERANCE") "±1%") (field (name "MANUFACTURER") "Stackpole Electronics Inc"))
      (libsource (lib "LimeMicroAltiumLib_schLib") (part "Res_0402"))
    )
    (comp (ref "R207")
      (value "10k, 1%")
      (footprint "RES0402")
      (fields (field (name "MANUFACTURER") "Yageo") (field (name "TOLERANCE") "±1%"))
      (libsource (lib "LimeMicroAltiumLib_schLib") (part "Res_0402"))
    )
    (comp (ref "R208")
      (value "0R")
      (footprint "RES0402")
      (fields (field (name "MANUFACTURER") "Yageo") (field (name "TOLERANCE") "Jumper"))
      (libsource (lib "LimeMicroAltiumLib_schLib") (part "Res_0402"))
    )
    (comp (ref "R209")
      (value "39k, 1%")
      (footprint "RES0402")
      (fields (field (name "MANUFACTURER") "Yageo") (field (name "TOLERANCE") "±1%"))
      (libsource (lib "LimeMicroAltiumLib_schLib") (part "Res_0402"))
    )
    (comp (ref "R210")
      (value "23.2k, 1%")
      (footprint "RES0402")
      (fields (field (name "TOLERANCE") "±1%") (field (name "MANUFACTURER") "Yageo"))
      (libsource (lib "LimeMicroAltiumLib_schLib") (part "Res_0402"))
    )
    (comp (ref "R211")
      (value "10k, 1%")
      (footprint "RES0402")
      (fields (field (name "MANUFACTURER") "Yageo") (field (name "TOLERANCE") "±1%"))
      (libsource (lib "LimeMicroAltiumLib_schLib") (part "Res_0402"))
    )
    (comp (ref "R212")
      (value "0R")
      (footprint "RES0402")
      (fields
        (field (name "ASSEMBLY INFO") "NF")
        (field (name "MANUFACTURER") "Yageo")
        (field (name "TOLERANCE") "Jumper")
      )
      (libsource (lib "LimeMicroAltiumLib_schLib") (part "Res_0402"))
    )
    (comp (ref "VD1")
      (value "SK36A")
      (footprint "DIODE_SMB")
      (description "Diode Schottky SMD SOD-523F")
      (fields (field (name "MANUFACTURER") "Micro Commercial Co"))
      (libsource (lib "LimeMicroAltiumLib_schLib") (part "DIODE_SCHOTTKY_SOD-523F"))
    )
  )
  (nets
    (net (code "1") (name "/FPF_VINSEL") (class "Default")
      (node (ref "IC25") (pin "D4") (pinfunction "Vin_SEL_D4") (pintype "passive"))
    )
    (net (code "2") (name "/FPGA_LED1_G") (class "Default")
      (node (ref "R168") (pin "1") (pinfunction "1_1") (pintype "passive"))
    )
    (net (code "3") (name "/FPGA_LED1_R") (class "Default")
      (node (ref "LED1") (pin "2") (pinfunction "2_2") (pintype "power_in"))
      (node (ref "LED1") (pin "3") (pinfunction "3_3") (pintype "power_in"))
      (node (ref "LEDS1") (pin "K1") (pinfunction "C_K1") (pintype "power_in"))
    )
    (net (code "4") (name "/FPGA_LED2_G") (class "Default")
      (node (ref "R170") (pin "1") (pinfunction "1_1") (pintype "passive"))
    )
    (net (code "5") (name "/FPGA_LED2_R") (class "Default")
      (node (ref "LED7") (pin "2") (pinfunction "2_2") (pintype "power_in"))
      (node (ref "LED7") (pin "3") (pinfunction "3_3") (pintype "power_in"))
      (node (ref "LEDS1") (pin "K2") (pinfunction "C_K2") (pintype "power_in"))
    )
    (net (code "6") (name "/FX3_LED_G") (class "Default")
      (node (ref "R169") (pin "1") (pinfunction "1_1") (pintype "passive"))
    )
    (net (code "7") (name "/FX3_LED_R") (class "Default")
      (node (ref "LED2") (pin "2") (pinfunction "2_2") (pintype "power_in"))
      (node (ref "LED2") (pin "3") (pinfunction "3_3") (pintype "power_in"))
      (node (ref "LEDS2") (pin "K1") (pinfunction "C_K1") (pintype "power_in"))
    )
    (net (code "8") (name "GND") (class "Default")
      (node (ref "C367") (pin "1") (pinfunction "1_1") (pintype "passive"))
      (node (ref "C368") (pin "1") (pinfunction "1_1") (pintype "passive"))
      (node (ref "C369") (pin "1") (pinfunction "1_1") (pintype "passive"))
      (node (ref "C370") (pin "1") (pinfunction "1_1") (pintype "passive"))
      (node (ref "C371") (pin "1") (pinfunction "1_1") (pintype "passive"))
      (node (ref "C372") (pin "2") (pinfunction "2_2") (pintype "passive"))
      (node (ref "C373") (pin "2") (pinfunction "2_2") (pintype "passive"))
      (node (ref "C374") (pin "1") (pinfunction "1_1") (pintype "passive"))
      (node (ref "C375") (pin "1") (pinfunction "1_1") (pintype "passive"))
      (node (ref "C376") (pin "1") (pinfunction "1_1") (pintype "passive"))
      (node (ref "C377") (pin "1") (pinfunction "1_1") (pintype "passive"))
      (node (ref "C379") (pin "1") (pinfunction "1_1") (pintype "passive"))
      (node (ref "C380") (pin "1") (pinfunction "1_1") (pintype "passive"))
      (node (ref "C381") (pin "2") (pinfunction "2_2") (pintype "passive"))
      (node (ref "C382") (pin "1") (pinfunction "1_1") (pintype "passive"))
      (node (ref "C383") (pin "1") (pinfunction "1_1") (pintype "passive"))
      (node (ref "C384") (pin "1") (pinfunction "1_1") (pintype "passive"))
      (node (ref "C385") (pin "1") (pinfunction "1_1") (pintype "passive"))
      (node (ref "C386") (pin "1") (pinfunction "1_1") (pintype "passive"))
      (node (ref "C387") (pin "1") (pinfunction "1_1") (pintype "passive"))
      (node (ref "C388") (pin "2") (pinfunction "2_2") (pintype "passive"))
      (node (ref "C389") (pin "2") (pinfunction "2_2") (pintype "passive"))
      (node (ref "C390") (pin "2") (pinfunction "2_2") (pintype "passive"))
      (node (ref "C391") (pin "2") (pinfunction "2_2") (pintype "passive"))
      (node (ref "C392") (pin "1") (pinfunction "1_1") (pintype "passive"))
      (node (ref "C393") (pin "1") (pinfunction "1_1") (pintype "passive"))
      (node (ref "C394") (pin "1") (pinfunction "1_1") (pintype "passive"))
      (node (ref "C395") (pin "2") (pinfunction "2_2") (pintype "passive"))
      (node (ref "C396") (pin "1") (pinfunction "1_1") (pintype "passive"))
      (node (ref "C397") (pin "1") (pinfunction "1_1") (pintype "passive"))
      (node (ref "C398") (pin "1") (pinfunction "1_1") (pintype "passive"))
      (node (ref "C400") (pin "1") (pinfunction "1_1") (pintype "passive"))
      (node (ref "C401") (pin "1") (pinfunction "1_1") (pintype "passive"))
      (node (ref "C402") (pin "1") (pinfunction "1_1") (pintype "passive"))
      (node (ref "C403") (pin "1") (pinfunction "1_1") (pintype "passive"))
      (node (ref "C404") (pin "1") (pinfunction "1_1") (pintype "passive"))
      (node (ref "C405") (pin "1") (pinfunction "1_1") (pintype "passive"))
      (node (ref "C406") (pin "1") (pinfunction "1_1") (pintype "passive"))
      (node (ref "C407") (pin "1") (pinfunction "1_1") (pintype "passive"))
      (node (ref "C408") (pin "2") (pinfunction "2_2") (pintype "passive"))
      (node (ref "C409") (pin "1") (pinfunction "1_1") (pintype "passive"))
      (node (ref "C410") (pin "1") (pinfunction "1_1") (pintype "passive"))
      (node (ref "C411") (pin "2") (pinfunction "2_2") (pintype "passive"))
      (node (ref "C412") (pin "2") (pinfunction "2_2") (pintype "passive"))
      (node (ref "C413") (pin "2") (pinfunction "2_2") (pintype "passive"))
      (node (ref "C414") (pin "1") (pinfunction "1_1") (pintype "passive"))
      (node (ref "C415") (pin "1") (pinfunction "1_1") (pintype "passive"))
      (node (ref "C416") (pin "1") (pinfunction "1_1") (pintype "passive"))
      (node (ref "C417") (pin "1") (pinfunction "1_1") (pintype "passive"))
      (node (ref "C418") (pin "1") (pinfunction "1_1") (pintype "passive"))
      (node (ref "C419") (pin "1") (pinfunction "1_1") (pintype "passive"))
      (node (ref "C420") (pin "1") (pinfunction "1_1") (pintype "passive"))
      (node (ref "C421") (pin "1") (pinfunction "1_1") (pintype "passive"))
      (node (ref "IC25") (pin "C2") (pinfunction "EN_C2") (pintype "passive"))
      (node (ref "IC25") (pin "D1") (pinfunction "GND_D1") (pintype "passive"))
      (node (ref "IC25") (pin "D2") (pinfunction "GND_D2") (pintype "passive"))
      (node (ref "IC25") (pin "D3") (pinfunction "DF_IN_D3") (pintype "passive"))
      (node (ref "IC26") (pin "4") (pinfunction "GND_4") (pintype "passive"))
      (node (ref "IC26") (pin "9") (pinfunction "PAD_9") (pintype "passive"))
      (node (ref "IC27") (pin "10") (pinfunction "PGND_10") (pintype "passive"))
      (node (ref "IC27") (pin "11") (pinfunction "PGND_11") (pintype "passive"))
      (node (ref "IC27") (pin "12") (pinfunction "PGND_12") (pintype "passive"))
      (node (ref "IC27") (pin "13") (pinfunction "PGND_13") (pintype "passive"))
      (node (ref "IC27") (pin "25") (pinfunction "GND_25") (pintype "passive"))
      (node (ref "IC27") (pin "4") (pinfunction "GND_4") (pintype "passive"))
      (node (ref "IC27") (pin "8") (pinfunction "PGND_8") (pintype "passive"))
      (node (ref "IC27") (pin "9") (pinfunction "PGND_9") (pintype "passive"))
      (node (ref "IC28") (pin "4") (pinfunction "GND_4") (pintype "passive"))
      (node (ref "IC28") (pin "9") (pinfunction "PAD_9") (pintype "passive"))
      (node (ref "IC29") (pin "11") (pinfunction "GND_11") (pintype "passive"))
      (node (ref "IC29") (pin "4") (pinfunction "PGND_4") (pintype "passive"))
      (node (ref "IC29") (pin "8") (pinfunction "GND_8") (pintype "passive"))
      (node (ref "IC30") (pin "4") (pinfunction "GND_4") (pintype "passive"))
      (node (ref "IC30") (pin "9") (pinfunction "PAD_9") (pintype "passive"))
      (node (ref "IC31") (pin "10") (pinfunction "PGND_10") (pintype "passive"))
      (node (ref "IC31") (pin "11") (pinfunction "PGND_11") (pintype "passive"))
      (node (ref "IC31") (pin "12") (pinfunction "PGND_12") (pintype "passive"))
      (node (ref "IC31") (pin "13") (pinfunction "PGND_13") (pintype "passive"))
      (node (ref "IC31") (pin "25") (pinfunction "GND_25") (pintype "passive"))
      (node (ref "IC31") (pin "4") (pinfunction "GND_4") (pintype "passive"))
      (node (ref "IC31") (pin "8") (pinfunction "PGND_8") (pintype "passive"))
      (node (ref "IC31") (pin "9") (pinfunction "PGND_9") (pintype "passive"))
      (node (ref "IC32") (pin "4") (pinfunction "GND_4") (pintype "passive"))
      (node (ref "IC32") (pin "9") (pinfunction "PAD_9") (pintype "passive"))
      (node (ref "IC33") (pin "4") (pinfunction "GND_4") (pintype "passive"))
      (node (ref "IC33") (pin "9") (pinfunction "PAD_9") (pintype "passive"))
      (node (ref "IC34") (pin "4") (pinfunction "GND_4") (pintype "passive"))
      (node (ref "IC34") (pin "9") (pinfunction "PAD_9") (pintype "passive"))
      (node (ref "IC35") (pin "3") (pinfunction "GND_3") (pintype "passive"))
      (node (ref "IC36") (pin "7") (pinfunction "GND_7") (pintype "passive"))
      (node (ref "IC36") (pin "9") (pinfunction "PAD_9") (pintype "passive"))
      (node (ref "J20") (pin "2") (pinfunction "2_2") (pintype "passive"))
      (node (ref "J20") (pin "3") (pinfunction "3_3") (pintype "passive"))
      (node (ref "J21") (pin "1") (pinfunction "1_1") (pintype "passive"))
      (node (ref "LED8") (pin "3") (pinfunction "3_3") (pintype "power_in"))
      (node (ref "LEDS2") (pin "K2") (pinfunction "C_K2") (pintype "power_in"))
      (node (ref "MECH1") (pin "MH1") (pinfunction "MH1_MH1") (pintype "passive"))
      (node (ref "MECH2") (pin "MH1") (pinfunction "MH1_MH1") (pintype "passive"))
      (node (ref "MECH3") (pin "MH1") (pinfunction "MH1_MH1") (pintype "passive"))
      (node (ref "MECH4") (pin "MH1") (pinfunction "MH1_MH1") (pintype "passive"))
      (node (ref "R175") (pin "2") (pinfunction "2_2") (pintype "passive"))
      (node (ref "R181") (pin "2") (pinfunction "2_2") (pintype "passive"))
      (node (ref "R182") (pin "2") (pinfunction "2_2") (pintype "passive"))
      (node (ref "R183") (pin "2") (pinfunction "2_2") (pintype "passive"))
      (node (ref "R184") (pin "1") (pinfunction "1_1") (pintype "passive"))
      (node (ref "R190") (pin "1") (pinfunction "1_1") (pintype "passive"))
      (node (ref "R196") (pin "2") (pinfunction "2_2") (pintype "passive"))
      (node (ref "R197") (pin "2") (pinfunction "2_2") (pintype "passive"))
      (node (ref "R198") (pin "1") (pinfunction "1_1") (pintype "passive"))
      (node (ref "R199") (pin "2") (pinfunction "2_2") (pintype "passive"))
      (node (ref "R200") (pin "2") (pinfunction "2_2") (pintype "passive"))
      (node (ref "R206") (pin "2") (pinfunction "2_2") (pintype "passive"))
      (node (ref "R207") (pin "2") (pinfunction "2_2") (pintype "passive"))
      (node (ref "R210") (pin "1") (pinfunction "1_1") (pintype "passive"))
    )
    (net (code "9") (name "Net-(C367-Pad2)") (class "Default")
      (node (ref "C367") (pin "2") (pinfunction "2_2") (pintype "passive"))
      (node (ref "FR56") (pin "2") (pinfunction "2_2") (pintype "passive"))
      (node (ref "IC25") (pin "A2") (pinfunction "Vout_A2") (pintype "passive"))
      (node (ref "IC25") (pin "A3") (pinfunction "Vout_A3") (pintype "passive"))
      (node (ref "IC25") (pin "B3") (pinfunction "Vout_B3") (pintype "passive"))
      (node (ref "IC25") (pin "C3") (pinfunction "Vout_C3") (pintype "passive"))
    )
    (net (code "10") (name "Net-(C373-Pad1)") (class "Default")
      (node (ref "C373") (pin "1") (pinfunction "1_1") (pintype "passive"))
      (node (ref "J20") (pin "1") (pinfunction "1_1") (pintype "passive"))
      (node (ref "J21") (pin "2") (pinfunction "2_2") (pintype "passive"))
      (node (ref "R172") (pin "2") (pinfunction "2_2") (pintype "passive"))
      (node (ref "VD1") (pin "A") (pinfunction "A_A") (pintype "passive"))
    )
    (net (code "11") (name "Net-(C378-Pad2)") (class "Default")
      (node (ref "C378") (pin "2") (pinfunction "2_2") (pintype "passive"))
      (node (ref "IC27") (pin "14") (pinfunction "SW_14") (pintype "passive"))
      (node (ref "IC27") (pin "26") (pinfunction "SW_26") (pintype "passive"))
      (node (ref "IC27") (pin "5") (pinfunction "SW_5") (pintype "passive"))
      (node (ref "IC27") (pin "6") (pinfunction "SW_6") (pintype "passive"))
      (node (ref "IC27") (pin "7") (pinfunction "SW_7") (pintype "passive"))
      (node (ref "L1") (pin "1") (pinfunction "1_1") (pintype "passive"))
    )
    (net (code "12") (name "Net-(C390-Pad1)") (class "Default")
      (node (ref "C390") (pin "1") (pinfunction "1_1") (pintype "passive"))
      (node (ref "R185") (pin "1") (pinfunction "1_1") (pintype "passive"))
    )
    (net (code "13") (name "Net-(C399-Pad2)") (class "Default")
      (node (ref "C399") (pin "2") (pinfunction "2_2") (pintype "passive"))
      (node (ref "IC31") (pin "14") (pinfunction "SW_14") (pintype "passive"))
      (node (ref "IC31") (pin "26") (pinfunction "SW_26") (pintype "passive"))
      (node (ref "IC31") (pin "5") (pinfunction "SW_5") (pintype "passive"))
      (node (ref "IC31") (pin "6") (pinfunction "SW_6") (pintype "passive"))
      (node (ref "IC31") (pin "7") (pinfunction "SW_7") (pintype "passive"))
      (node (ref "L2") (pin "1") (pinfunction "1_1") (pintype "passive"))
    )
    (net (code "14") (name "Net-(C412-Pad1)") (class "Default")
      (node (ref "C412") (pin "1") (pinfunction "1_1") (pintype "passive"))
      (node (ref "R201") (pin "1") (pinfunction "1_1") (pintype "passive"))
    )
    (net (code "15") (name "Net-(C418-Pad2)") (class "Default")
      (node (ref "C418") (pin "2") (pinfunction "2_2") (pintype "passive"))
      (node (ref "FR63") (pin "2") (pinfunction "2_2") (pintype "passive"))
      (node (ref "R208") (pin "2") (pinfunction "2_2") (pintype "passive"))
    )
    (net (code "16") (name "Net-(IC26-ADJ{slash}NC)") (class "Default")
      (node (ref "IC26") (pin "3") (pinfunction "ADJ/NC_3") (pintype "passive"))
      (node (ref "R174") (pin "1") (pinfunction "1_1") (pintype "passive"))
      (node (ref "R175") (pin "1") (pinfunction "1_1") (pintype "passive"))
    )
    (net (code "17") (name "Net-(IC26-OUT)") (class "Default")
      (node (ref "C377") (pin "2") (pinfunction "2_2") (pintype "passive"))
      (node (ref "IC26") (pin "1") (pinfunction "OUT_1") (pintype "output"))
      (node (ref "R173") (pin "2") (pinfunction "2_2") (pintype "passive"))
      (node (ref "R174") (pin "2") (pinfunction "2_2") (pintype "passive"))
    )
    (net (code "18") (name "Net-(IC27-BST)") (class "Default")
      (node (ref "C378") (pin "1") (pinfunction "1_1") (pintype "passive"))
      (node (ref "IC27") (pin "15") (pinfunction "BST_15") (pintype "passive"))
    )
    (net (code "19") (name "Net-(IC27-COMP)") (class "Default")
      (node (ref "C389") (pin "1") (pinfunction "1_1") (pintype "passive"))
      (node (ref "IC27") (pin "1") (pinfunction "COMP_1") (pintype "passive"))
      (node (ref "R185") (pin "2") (pinfunction "2_2") (pintype "passive"))
    )
    (net (code "20") (name "Net-(IC27-FB)") (class "Default")
      (node (ref "IC27") (pin "2") (pinfunction "FB_2") (pintype "passive"))
      (node (ref "R180") (pin "2") (pinfunction "2_2") (pintype "passive"))
      (node (ref "R184") (pin "2") (pinfunction "2_2") (pintype "passive"))
    )
    (net (code "21") (name "Net-(IC27-RT)") (class "Default")
      (node (ref "IC27") (pin "22") (pinfunction "RT_22") (pintype "passive"))
      (node (ref "R183") (pin "1") (pinfunction "1_1") (pintype "passive"))
    )
    (net (code "22") (name "Net-(IC27-SS)") (class "Default")
      (node (ref "C391") (pin "1") (pinfunction "1_1") (pintype "passive"))
      (node (ref "IC27") (pin "24") (pinfunction "SS_24") (pintype "passive"))
    )
    (net (code "23") (name "Net-(IC27-SYNC)") (class "Default")
      (node (ref "IC27") (pin "23") (pinfunction "SYNC_23") (pintype "passive"))
      (node (ref "R181") (pin "1") (pinfunction "1_1") (pintype "passive"))
    )
    (net (code "24") (name "Net-(IC27-VREG)") (class "Default")
      (node (ref "C388") (pin "1") (pinfunction "1_1") (pintype "passive"))
      (node (ref "IC27") (pin "3") (pinfunction "VREG_3") (pintype "passive"))
    )
    (net (code "25") (name "Net-(IC28-ADJ{slash}NC)") (class "Default")
      (node (ref "IC28") (pin "3") (pinfunction "ADJ/NC_3") (pintype "passive"))
      (node (ref "R179") (pin "1") (pinfunction "1_1") (pintype "passive"))
      (node (ref "R182") (pin "1") (pinfunction "1_1") (pintype "passive"))
    )
    (net (code "26") (name "Net-(IC28-EN)") (class "Default")
      (node (ref "C383") (pin "2") (pinfunction "2_2") (pintype "passive"))
      (node (ref "FR58") (pin "2") (pinfunction "2_2") (pintype "passive"))
      (node (ref "IC28") (pin "5") (pinfunction "EN_5") (pintype "input"))
      (node (ref "IC28") (pin "8") (pinfunction "IN_8") (pintype "input"))
    )
    (net (code "27") (name "Net-(IC28-OUT)") (class "Default")
      (node (ref "C384") (pin "2") (pinfunction "2_2") (pintype "passive"))
      (node (ref "IC28") (pin "1") (pinfunction "OUT_1") (pintype "output"))
      (node (ref "R178") (pin "2") (pinfunction "2_2") (pintype "passive"))
      (node (ref "R179") (pin "2") (pinfunction "2_2") (pintype "passive"))
    )
    (net (code "28") (name "Net-(IC29-S3)") (class "Default")
      (node (ref "IC29") (pin "7") (pinfunction "S3_7") (pintype "passive"))
      (node (ref "R187") (pin "2") (pinfunction "2_2") (pintype "passive"))
    )
    (net (code "29") (name "Net-(IC29-S5)") (class "Default")
      (node (ref "IC29") (pin "9") (pinfunction "S5_9") (pintype "passive"))
      (node (ref "R186") (pin "2") (pinfunction "2_2") (pintype "passive"))
    )
    (net (code "30") (name "Net-(IC30-ADJ{slash}NC)") (class "Default")
      (node (ref "IC30") (pin "3") (pinfunction "ADJ/NC_3") (pintype "passive"))
      (node (ref "R189") (pin "2") (pinfunction "2_2") (pintype "passive"))
      (node (ref "R190") (pin "2") (pinfunction "2_2") (pintype "passive"))
    )
    (net (code "31") (name "Net-(IC30-EN)") (class "Default")
      (node (ref "C397") (pin "2") (pinfunction "2_2") (pintype "passive"))
      (node (ref "FR59") (pin "2") (pinfunction "2_2") (pintype "passive"))
      (node (ref "IC30") (pin "5") (pinfunction "EN_5") (pintype "input"))
      (node (ref "IC30") (pin "8") (pinfunction "IN_8") (pintype "input"))
    )
    (net (code "32") (name "Net-(IC30-OUT)") (class "Default")
      (node (ref "C398") (pin "2") (pinfunction "2_2") (pintype "passive"))
      (node (ref "IC30") (pin "1") (pinfunction "OUT_1") (pintype "output"))
      (node (ref "R188") (pin "2") (pinfunction "2_2") (pintype "passive"))
      (node (ref "R189") (pin "1") (pinfunction "1_1") (pintype "passive"))
    )
    (net (code "33") (name "Net-(IC31-BST)") (class "Default")
      (node (ref "C399") (pin "1") (pinfunction "1_1") (pintype "passive"))
      (node (ref "IC31") (pin "15") (pinfunction "BST_15") (pintype "passive"))
    )
    (net (code "34") (name "Net-(IC31-COMP)") (class "Default")
      (node (ref "C411") (pin "1") (pinfunction "1_1") (pintype "passive"))
      (node (ref "IC31") (pin "1") (pinfunction "COMP_1") (pintype "passive"))
      (node (ref "R201") (pin "2") (pinfunction "2_2") (pintype "passive"))
    )
    (net (code "35") (name "Net-(IC31-FB)") (class "Default")
      (node (ref "IC31") (pin "2") (pinfunction "FB_2") (pintype "passive"))
      (node (ref "R195") (pin "2") (pinfunction "2_2") (pintype "passive"))
      (node (ref "R200") (pin "1") (pinfunction "1_1") (pintype "passive"))
    )
    (net (code "36") (name "Net-(IC31-RT)") (class "Default")
      (node (ref "IC31") (pin "22") (pinfunction "RT_22") (pintype "passive"))
      (node (ref "R199") (pin "1") (pinfunction "1_1") (pintype "passive"))
    )
    (net (code "37") (name "Net-(IC31-SS)") (class "Default")
      (node (ref "C413") (pin "1") (pinfunction "1_1") (pintype "passive"))
      (node (ref "IC31") (pin "24") (pinfunction "SS_24") (pintype "passive"))
    )
    (net (code "38") (name "Net-(IC31-SYNC)") (class "Default")
      (node (ref "IC31") (pin "23") (pinfunction "SYNC_23") (pintype "passive"))
      (node (ref "R196") (pin "1") (pinfunction "1_1") (pintype "passive"))
    )
    (net (code "39") (name "Net-(IC31-VREG)") (class "Default")
      (node (ref "C408") (pin "1") (pinfunction "1_1") (pintype "passive"))
      (node (ref "IC31") (pin "3") (pinfunction "VREG_3") (pintype "passive"))
    )
    (net (code "40") (name "Net-(IC32-ADJ{slash}NC)") (class "Default")
      (node (ref "IC32") (pin "3") (pinfunction "ADJ/NC_3") (pintype "passive"))
      (node (ref "R193") (pin "1") (pinfunction "1_1") (pintype "passive"))
      (node (ref "R197") (pin "1") (pinfunction "1_1") (pintype "passive"))
    )
    (net (code "41") (name "Net-(IC32-OUT)") (class "Default")
      (node (ref "C402") (pin "2") (pinfunction "2_2") (pintype "passive"))
      (node (ref "IC32") (pin "1") (pinfunction "OUT_1") (pintype "output"))
      (node (ref "R191") (pin "2") (pinfunction "2_2") (pintype "passive"))
      (node (ref "R193") (pin "2") (pinfunction "2_2") (pintype "passive"))
    )
    (net (code "42") (name "Net-(IC33-ADJ{slash}NC)") (class "Default")
      (node (ref "IC33") (pin "3") (pinfunction "ADJ/NC_3") (pintype "passive"))
      (node (ref "R194") (pin "1") (pinfunction "1_1") (pintype "passive"))
      (node (ref "R198") (pin "2") (pinfunction "2_2") (pintype "passive"))
    )
    (net (code "43") (name "Net-(IC33-EN)") (class "Default")
      (node (ref "C404") (pin "2") (pinfunction "2_2") (pintype "passive"))
      (node (ref "FR60") (pin "2") (pinfunction "2_2") (pintype "passive"))
      (node (ref "IC33") (pin "5") (pinfunction "EN_5") (pintype "input"))
      (node (ref "IC33") (pin "8") (pinfunction "IN_8") (pintype "input"))
    )
    (net (code "44") (name "Net-(IC33-OUT)") (class "Default")
      (node (ref "C405") (pin "2") (pinfunction "2_2") (pintype "passive"))
      (node (ref "IC33") (pin "1") (pinfunction "OUT_1") (pintype "output"))
      (node (ref "R192") (pin "2") (pinfunction "2_2") (pintype "passive"))
      (node (ref "R194") (pin "2") (pinfunction "2_2") (pintype "passive"))
    )
    (net (code "45") (name "Net-(IC34-ADJ{slash}NC)") (class "Default")
      (node (ref "IC34") (pin "3") (pinfunction "ADJ/NC_3") (pintype "passive"))
      (node (ref "R203") (pin "1") (pinfunction "1_1") (pintype "passive"))
      (node (ref "R206") (pin "1") (pinfunction "1_1") (pintype "passive"))
    )
    (net (code "46") (name "Net-(IC34-OUT)") (class "Default")
      (node (ref "C410") (pin "2") (pinfunction "2_2") (pintype "passive"))
      (node (ref "IC34") (pin "1") (pinfunction "OUT_1") (pintype "output"))
      (node (ref "R202") (pin "2") (pinfunction "2_2") (pintype "passive"))
      (node (ref "R203") (pin "2") (pinfunction "2_2") (pintype "passive"))
    )
    (net (code "47") (name "Net-(IC35-ADJUST)") (class "Default")
      (node (ref "IC35") (pin "5") (pinfunction "ADJUST_5") (pintype "passive"))
      (node (ref "R205") (pin "2") (pinfunction "2_2") (pintype "passive"))
      (node (ref "R207") (pin "1") (pinfunction "1_1") (pintype "passive"))
    )
    (net (code "48") (name "Net-(IC35-IN)") (class "Default")
      (node (ref "C416") (pin "2") (pinfunction "2_2") (pintype "passive"))
      (node (ref "FR61") (pin "2") (pinfunction "2_2") (pintype "passive"))
      (node (ref "IC35") (pin "2") (pinfunction "IN_2") (pintype "passive"))
    )
    (net (code "49") (name "Net-(IC35-OUT)") (class "Default")
      (node (ref "C415") (pin "2") (pinfunction "2_2") (pintype "passive"))
      (node (ref "IC35") (pin "4") (pinfunction "OUT_4") (pintype "passive"))
      (node (ref "R204") (pin "2") (pinfunction "2_2") (pintype "passive"))
      (node (ref "R205") (pin "1") (pinfunction "1_1") (pintype "passive"))
    )
    (net (code "50") (name "Net-(IC36-ADJ{slash}BYP)") (class "Default")
      (node (ref "IC36") (pin "8") (pinfunction "ADJ/BYP_8") (pintype "input"))
      (node (ref "R209") (pin "2") (pinfunction "2_2") (pintype "passive"))
      (node (ref "R210") (pin "2") (pinfunction "2_2") (pintype "passive"))
    )
    (net (code "51") (name "Net-(IC36-EN)") (class "Default")
      (node (ref "C421") (pin "2") (pinfunction "2_2") (pintype "passive"))
      (node (ref "IC36") (pin "1") (pinfunction "EN_1") (pintype "input"))
      (node (ref "R211") (pin "2") (pinfunction "2_2") (pintype "passive"))
      (node (ref "R212") (pin "1") (pinfunction "1_1") (pintype "passive"))
    )
    (net (code "52") (name "Net-(IC36-VIN)") (class "Default")
      (node (ref "C420") (pin "2") (pinfunction "2_2") (pintype "passive"))
      (node (ref "FR62") (pin "2") (pinfunction "2_2") (pintype "passive"))
      (node (ref "IC36") (pin "3") (pinfunction "VIN_3") (pintype "input"))
    )
    (net (code "53") (name "Net-(IC36-VOUT)") (class "Default")
      (node (ref "C417") (pin "2") (pinfunction "2_2") (pintype "passive"))
      (node (ref "FR63") (pin "1") (pinfunction "1_1") (pintype "passive"))
      (node (ref "IC36") (pin "5") (pinfunction "VOUT_5") (pintype "output"))
      (node (ref "R209") (pin "1") (pinfunction "1_1") (pintype "passive"))
    )
    (net (code "54") (name "Net-(LED1-Pad1)") (class "Default")
      (node (ref "LED1") (pin "1") (pinfunction "1_1") (pintype "power_in"))
      (node (ref "LED1") (pin "4") (pinfunction "4_4") (pintype "power_in"))
      (node (ref "LEDS1") (pin "A1") (pinfunction "A_A1") (pintype "power_in"))
      (node (ref "R168") (pin "2") (pinfunction "2_2") (pintype "passive"))
    )
    (net (code "55") (name "Net-(LED2-Pad1)") (class "Default")
      (node (ref "LED2") (pin "1") (pinfunction "1_1") (pintype "power_in"))
      (node (ref "LED2") (pin "4") (pinfunction "4_4") (pintype "power_in"))
      (node (ref "LEDS2") (pin "A1") (pinfunction "A_A1") (pintype "power_in"))
      (node (ref "R169") (pin "2") (pinfunction "2_2") (pintype "passive"))
    )
    (net (code "56") (name "Net-(LED7-Pad1)") (class "Default")
      (node (ref "LED7") (pin "1") (pinfunction "1_1") (pintype "power_in"))
      (node (ref "LED7") (pin "4") (pinfunction "4_4") (pintype "power_in"))
      (node (ref "LEDS1") (pin "A2") (pinfunction "A_A2") (pintype "power_in"))
      (node (ref "R170") (pin "2") (pinfunction "2_2") (pintype "passive"))
    )
    (net (code "57") (name "Net-(LED8-Pad1)") (class "Default")
      (node (ref "LED8") (pin "1") (pinfunction "1_1") (pintype "power_in"))
      (node (ref "LEDS2") (pin "A2") (pinfunction "A_A2") (pintype "power_in"))
      (node (ref "R171") (pin "2") (pinfunction "2_2") (pintype "passive"))
    )
    (net (code "58") (name "VCC1P2") (class "Default")
      (node (ref "C406") (pin "2") (pinfunction "2_2") (pintype "passive"))
      (node (ref "C407") (pin "2") (pinfunction "2_2") (pintype "passive"))
      (node (ref "L2") (pin "2") (pinfunction "2_2") (pintype "passive"))
      (node (ref "R195") (pin "1") (pinfunction "1_1") (pintype "passive"))
    )
    (net (code "59") (name "VCC1P4_LMS") (class "Default")
      (node (ref "R188") (pin "1") (pinfunction "1_1") (pintype "passive"))
    )
    (net (code "60") (name "VCC1P8") (class "Default")
      (node (ref "R202") (pin "1") (pinfunction "1_1") (pintype "passive"))
    )
    (net (code "61") (name "VCC1P8_DDR2") (class "Default")
      (node (ref "C387") (pin "2") (pinfunction "2_2") (pintype "passive"))
      (node (ref "IC29") (pin "1") (pinfunction "VDDQSNS_1") (pintype "passive"))
      (node (ref "IC29") (pin "2") (pinfunction "VLDOIN_2") (pintype "passive"))
      (node (ref "R191") (pin "1") (pinfunction "1_1") (pintype "passive"))
    )
    (net (code "62") (name "VCC1P8_LMS") (class "Default")
      (node (ref "R178") (pin "1") (pinfunction "1_1") (pintype "passive"))
    )
    (net (code "63") (name "VCC1P25_LMS") (class "Default")
      (node (ref "R192") (pin "1") (pinfunction "1_1") (pintype "passive"))
    )
    (net (code "64") (name "VCC1P25_LMS_DIG") (class "Default")
      (node (ref "R204") (pin "1") (pinfunction "1_1") (pintype "passive"))
    )
    (net (code "65") (name "VCC2P5") (class "Default")
      (node (ref "R173") (pin "1") (pinfunction "1_1") (pintype "passive"))
      (node (ref "R177") (pin "2") (pinfunction "2_2") (pintype "passive"))
      (node (ref "R211") (pin "1") (pinfunction "1_1") (pintype "passive"))
    )
    (net (code "66") (name "VCC3P3") (class "Default")
      (node (ref "C376") (pin "2") (pinfunction "2_2") (pintype "passive"))
      (node (ref "C382") (pin "2") (pinfunction "2_2") (pintype "passive"))
      (node (ref "C385") (pin "2") (pinfunction "2_2") (pintype "passive"))
      (node (ref "C386") (pin "2") (pinfunction "2_2") (pintype "passive"))
      (node (ref "C394") (pin "2") (pinfunction "2_2") (pintype "passive"))
      (node (ref "C396") (pin "2") (pinfunction "2_2") (pintype "passive"))
      (node (ref "C401") (pin "2") (pinfunction "2_2") (pintype "passive"))
      (node (ref "C403") (pin "2") (pinfunction "2_2") (pintype "passive"))
      (node (ref "C409") (pin "2") (pinfunction "2_2") (pintype "passive"))
      (node (ref "C414") (pin "2") (pinfunction "2_2") (pintype "passive"))
      (node (ref "FR58") (pin "1") (pinfunction "1_1") (pintype "passive"))
      (node (ref "FR59") (pin "1") (pinfunction "1_1") (pintype "passive"))
      (node (ref "FR60") (pin "1") (pinfunction "1_1") (pintype "passive"))
      (node (ref "FR61") (pin "1") (pinfunction "1_1") (pintype "passive"))
      (node (ref "IC26") (pin "5") (pinfunction "EN_5") (pintype "input"))
      (node (ref "IC26") (pin "8") (pinfunction "IN_8") (pintype "input"))
      (node (ref "IC29") (pin "10") (pinfunction "VIN_10") (pintype "passive"))
      (node (ref "IC32") (pin "5") (pinfunction "EN_5") (pintype "input"))
      (node (ref "IC32") (pin "8") (pinfunction "IN_8") (pintype "input"))
      (node (ref "IC34") (pin "5") (pinfunction "EN_5") (pintype "input"))
      (node (ref "IC34") (pin "8") (pinfunction "IN_8") (pintype "input"))
      (node (ref "L1") (pin "2") (pinfunction "2_2") (pintype "passive"))
      (node (ref "R171") (pin "1") (pinfunction "1_1") (pintype "passive"))
      (node (ref "R176") (pin "2") (pinfunction "2_2") (pintype "passive"))
      (node (ref "R180") (pin "1") (pinfunction "1_1") (pintype "passive"))
      (node (ref "R186") (pin "1") (pinfunction "1_1") (pintype "passive"))
      (node (ref "R187") (pin "1") (pinfunction "1_1") (pintype "passive"))
    )
    (net (code "67") (name "VCC3P3_CLK") (class "Default")
      (node (ref "R208") (pin "1") (pinfunction "1_1") (pintype "passive"))
    )
    (net (code "68") (name "VCC5P0_USB") (class "Default")
      (node (ref "C375") (pin "2") (pinfunction "2_2") (pintype "passive"))
      (node (ref "IC25") (pin "A1") (pinfunction "Vbus_A1") (pintype "passive"))
      (node (ref "IC25") (pin "B1") (pinfunction "Vbus_B1") (pintype "passive"))
      (node (ref "IC25") (pin "C1") (pinfunction "Vbus_C1") (pintype "passive"))
      (node (ref "R167") (pin "2") (pinfunction "2_2") (pintype "passive"))
    )
    (net (code "69") (name "VCC_EXT") (class "Default")
      (node (ref "C374") (pin "2") (pinfunction "2_2") (pintype "passive"))
      (node (ref "IC25") (pin "A4") (pinfunction "Vin_A4") (pintype "passive"))
      (node (ref "IC25") (pin "B4") (pinfunction "Vin_B4") (pintype "passive"))
      (node (ref "IC25") (pin "C4") (pinfunction "Vin_C4") (pintype "passive"))
      (node (ref "R166") (pin "2") (pinfunction "2_2") (pintype "passive"))
      (node (ref "R172") (pin "1") (pinfunction "1_1") (pintype "passive"))
      (node (ref "VD1") (pin "K") (pinfunction "K_K") (pintype "passive"))
    )
    (net (code "70") (name "VCC_INT") (class "Default")
      (node (ref "C368") (pin "2") (pinfunction "2_2") (pintype "passive"))
      (node (ref "C369") (pin "2") (pinfunction "2_2") (pintype "passive"))
      (node (ref "C370") (pin "2") (pinfunction "2_2") (pintype "passive"))
      (node (ref "C371") (pin "2") (pinfunction "2_2") (pintype "passive"))
      (node (ref "C372") (pin "1") (pinfunction "1_1") (pintype "passive"))
      (node (ref "C379") (pin "2") (pinfunction "2_2") (pintype "passive"))
      (node (ref "C400") (pin "2") (pinfunction "2_2") (pintype "passive"))
      (node (ref "C419") (pin "2") (pinfunction "2_2") (pintype "passive"))
      (node (ref "FR56") (pin "1") (pinfunction "1_1") (pintype "passive"))
      (node (ref "FR62") (pin "1") (pinfunction "1_1") (pintype "passive"))
      (node (ref "IC27") (pin "16") (pinfunction "PVIN_16") (pintype "passive"))
      (node (ref "IC27") (pin "17") (pinfunction "PVIN_17") (pintype "passive"))
      (node (ref "IC27") (pin "18") (pinfunction "PVIN_18") (pintype "passive"))
      (node (ref "IC27") (pin "19") (pinfunction "PVIN_19") (pintype "passive"))
      (node (ref "IC27") (pin "20") (pinfunction "EN_20") (pintype "passive"))
      (node (ref "IC31") (pin "16") (pinfunction "PVIN_16") (pintype "passive"))
      (node (ref "IC31") (pin "17") (pinfunction "PVIN_17") (pintype "passive"))
      (node (ref "IC31") (pin "18") (pinfunction "PVIN_18") (pintype "passive"))
      (node (ref "IC31") (pin "19") (pinfunction "PVIN_19") (pintype "passive"))
      (node (ref "IC31") (pin "20") (pinfunction "EN_20") (pintype "passive"))
      (node (ref "J21") (pin "3") (pinfunction "3_3") (pintype "passive"))
      (node (ref "R166") (pin "1") (pinfunction "1_1") (pintype "passive"))
      (node (ref "R167") (pin "1") (pinfunction "1_1") (pintype "passive"))
    )
    (net (code "71") (name "VDIO_LMS") (class "Default")
      (node (ref "C380") (pin "2") (pinfunction "2_2") (pintype "passive"))
      (node (ref "C381") (pin "1") (pinfunction "1_1") (pintype "passive"))
      (node (ref "FR57") (pin "2") (pinfunction "2_2") (pintype "passive"))
    )
    (net (code "72") (name "VDIO_LMS_FPGA") (class "Default")
      (node (ref "FR57") (pin "1") (pinfunction "1_1") (pintype "passive"))
      (node (ref "R176") (pin "1") (pinfunction "1_1") (pintype "passive"))
      (node (ref "R177") (pin "1") (pinfunction "1_1") (pintype "passive"))
      (node (ref "R212") (pin "2") (pinfunction "2_2") (pintype "passive"))
    )
    (net (code "73") (name "VREF_DDR2") (class "Default")
      (node (ref "C395") (pin "1") (pinfunction "1_1") (pintype "passive"))
      (node (ref "IC29") (pin "6") (pinfunction "VTTREF_6") (pintype "passive"))
    )
    (net (code "74") (name "VTT_DDR2") (class "Default")
      (node (ref "C392") (pin "2") (pinfunction "2_2") (pintype "passive"))
      (node (ref "C393") (pin "2") (pinfunction "2_2") (pintype "passive"))
      (node (ref "IC29") (pin "3") (pinfunction "VTT_3") (pintype "passive"))
      (node (ref "IC29") (pin "5") (pinfunction "VTTSNS_5") (pintype "passive"))
    )
    (net (code "75") (name "unconnected-(F1-Pad1)") (class "Default")
      (node (ref "F1") (pin "1") (pintype "passive+no_connect"))
    )
    (net (code "76") (name "unconnected-(F2-Pad1)") (class "Default")
      (node (ref "F2") (pin "1") (pintype "passive+no_connect"))
    )
    (net (code "77") (name "unconnected-(F3-Pad1)") (class "Default")
      (node (ref "F3") (pin "1") (pintype "passive+no_connect"))
    )
    (net (code "78") (name "unconnected-(F4-Pad1)") (class "Default")
      (node (ref "F4") (pin "1") (pintype "passive+no_connect"))
    )
    (net (code "79") (name "unconnected-(IC25-Other_Vin_AVA-PadB2)") (class "Default")
      (node (ref "IC25") (pin "B2") (pinfunction "Other_Vin_AVA_B2") (pintype "passive+no_connect"))
    )
    (net (code "80") (name "unconnected-(IC26-NC-Pad2)") (class "Default")
      (node (ref "IC26") (pin "2") (pinfunction "NC_2") (pintype "passive+no_connect"))
    )
    (net (code "81") (name "unconnected-(IC26-NC-Pad6)") (class "Default")
      (node (ref "IC26") (pin "6") (pinfunction "NC_6") (pintype "passive+no_connect"))
    )
    (net (code "82") (name "unconnected-(IC26-NC-Pad7)") (class "Default")
      (node (ref "IC26") (pin "7") (pinfunction "NC_7") (pintype "passive+no_connect"))
    )
    (net (code "83") (name "unconnected-(IC27-PGOOD-Pad21)") (class "Default")
      (node (ref "IC27") (pin "21") (pinfunction "PGOOD_21") (pintype "passive+no_connect"))
    )
    (net (code "84") (name "unconnected-(IC28-NC-Pad2)") (class "Default")
      (node (ref "IC28") (pin "2") (pinfunction "NC_2") (pintype "passive+no_connect"))
    )
    (net (code "85") (name "unconnected-(IC28-NC-Pad6)") (class "Default")
      (node (ref "IC28") (pin "6") (pinfunction "NC_6") (pintype "passive+no_connect"))
    )
    (net (code "86") (name "unconnected-(IC28-NC-Pad7)") (class "Default")
      (node (ref "IC28") (pin "7") (pinfunction "NC_7") (pintype "passive+no_connect"))
    )
    (net (code "87") (name "unconnected-(IC30-NC-Pad2)") (class "Default")
      (node (ref "IC30") (pin "2") (pinfunction "NC_2") (pintype "passive+no_connect"))
    )
    (net (code "88") (name "unconnected-(IC30-NC-Pad6)") (class "Default")
      (node (ref "IC30") (pin "6") (pinfunction "NC_6") (pintype "passive+no_connect"))
    )
    (net (code "89") (name "unconnected-(IC30-NC-Pad7)") (class "Default")
      (node (ref "IC30") (pin "7") (pinfunction "NC_7") (pintype "passive+no_connect"))
    )
    (net (code "90") (name "unconnected-(IC31-PGOOD-Pad21)") (class "Default")
      (node (ref "IC31") (pin "21") (pinfunction "PGOOD_21") (pintype "passive+no_connect"))
    )
    (net (code "91") (name "unconnected-(IC32-NC-Pad2)") (class "Default")
      (node (ref "IC32") (pin "2") (pinfunction "NC_2") (pintype "passive+no_connect"))
    )
    (net (code "92") (name "unconnected-(IC32-NC-Pad6)") (class "Default")
      (node (ref "IC32") (pin "6") (pinfunction "NC_6") (pintype "passive+no_connect"))
    )
    (net (code "93") (name "unconnected-(IC32-NC-Pad7)") (class "Default")
      (node (ref "IC32") (pin "7") (pinfunction "NC_7") (pintype "passive+no_connect"))
    )
    (net (code "94") (name "unconnected-(IC33-NC-Pad2)") (class "Default")
      (node (ref "IC33") (pin "2") (pinfunction "NC_2") (pintype "passive+no_connect"))
    )
    (net (code "95") (name "unconnected-(IC33-NC-Pad6)") (class "Default")
      (node (ref "IC33") (pin "6") (pinfunction "NC_6") (pintype "passive+no_connect"))
    )
    (net (code "96") (name "unconnected-(IC33-NC-Pad7)") (class "Default")
      (node (ref "IC33") (pin "7") (pinfunction "NC_7") (pintype "passive+no_connect"))
    )
    (net (code "97") (name "unconnected-(IC34-NC-Pad2)") (class "Default")
      (node (ref "IC34") (pin "2") (pinfunction "NC_2") (pintype "passive+no_connect"))
    )
    (net (code "98") (name "unconnected-(IC34-NC-Pad6)") (class "Default")
      (node (ref "IC34") (pin "6") (pinfunction "NC_6") (pintype "passive+no_connect"))
    )
    (net (code "99") (name "unconnected-(IC34-NC-Pad7)") (class "Default")
      (node (ref "IC34") (pin "7") (pinfunction "NC_7") (pintype "passive+no_connect"))
    )
    (net (code "100") (name "unconnected-(IC35-NC-Pad1)") (class "Default")
      (node (ref "IC35") (pin "1") (pinfunction "NC_1") (pintype "passive+no_connect"))
    )
    (net (code "101") (name "unconnected-(IC36-NC-Pad2)") (class "Default")
      (node (ref "IC36") (pin "2") (pinfunction "NC_2") (pintype "passive+no_connect"))
    )
    (net (code "102") (name "unconnected-(IC36-NC-Pad4)") (class "Default")
      (node (ref "IC36") (pin "4") (pinfunction "NC_4") (pintype "passive+no_connect"))
    )
    (net (code "103") (name "unconnected-(IC36-NC-Pad6)") (class "Default")
      (node (ref "IC36") (pin "6") (pinfunction "NC_6") (pintype "passive+no_connect"))
    )
    (net (code "104") (name "unconnected-(LED3-C-PadK)") (class "Default")
      (node (ref "LED3") (pin "K") (pinfunction "C_K") (pintype "power_in+no_connect"))
    )
    (net (code "105") (name "unconnected-(LED3-PadA)") (class "Default")
      (node (ref "LED3") (pin "A") (pinfunction "A_A") (pintype "power_in+no_connect"))
    )
    (net (code "106") (name "unconnected-(LED4-C-PadK)") (class "Default")
      (node (ref "LED4") (pin "K") (pinfunction "C_K") (pintype "power_in+no_connect"))
    )
    (net (code "107") (name "unconnected-(LED4-PadA)") (class "Default")
      (node (ref "LED4") (pin "A") (pinfunction "A_A") (pintype "power_in+no_connect"))
    )
    (net (code "108") (name "unconnected-(LED5-C-PadK)") (class "Default")
      (node (ref "LED5") (pin "K") (pinfunction "C_K") (pintype "power_in+no_connect"))
    )
    (net (code "109") (name "unconnected-(LED5-PadA)") (class "Default")
      (node (ref "LED5") (pin "A") (pinfunction "A_A") (pintype "power_in+no_connect"))
    )
    (net (code "110") (name "unconnected-(LED6-C-PadK)") (class "Default")
      (node (ref "LED6") (pin "K") (pinfunction "C_K") (pintype "power_in+no_connect"))
    )
    (net (code "111") (name "unconnected-(LED6-PadA)") (class "Default")
      (node (ref "LED6") (pin "A") (pinfunction "A_A") (pintype "power_in+no_connect"))
    )
    (net (code "112") (name "unconnected-(LED8-Pad2)") (class "Default")
      (node (ref "LED8") (pin "2") (pinfunction "2_2") (pintype "power_in+no_connect"))
    )
    (net (code "113") (name "unconnected-(LED8-Pad4)") (class "Default")
      (node (ref "LED8") (pin "4") (pinfunction "4_4") (pintype "power_in+no_connect"))
    )
  )
)
